# plaits_v50.net
KiCad netlist of a schematic drawn in EAGLE
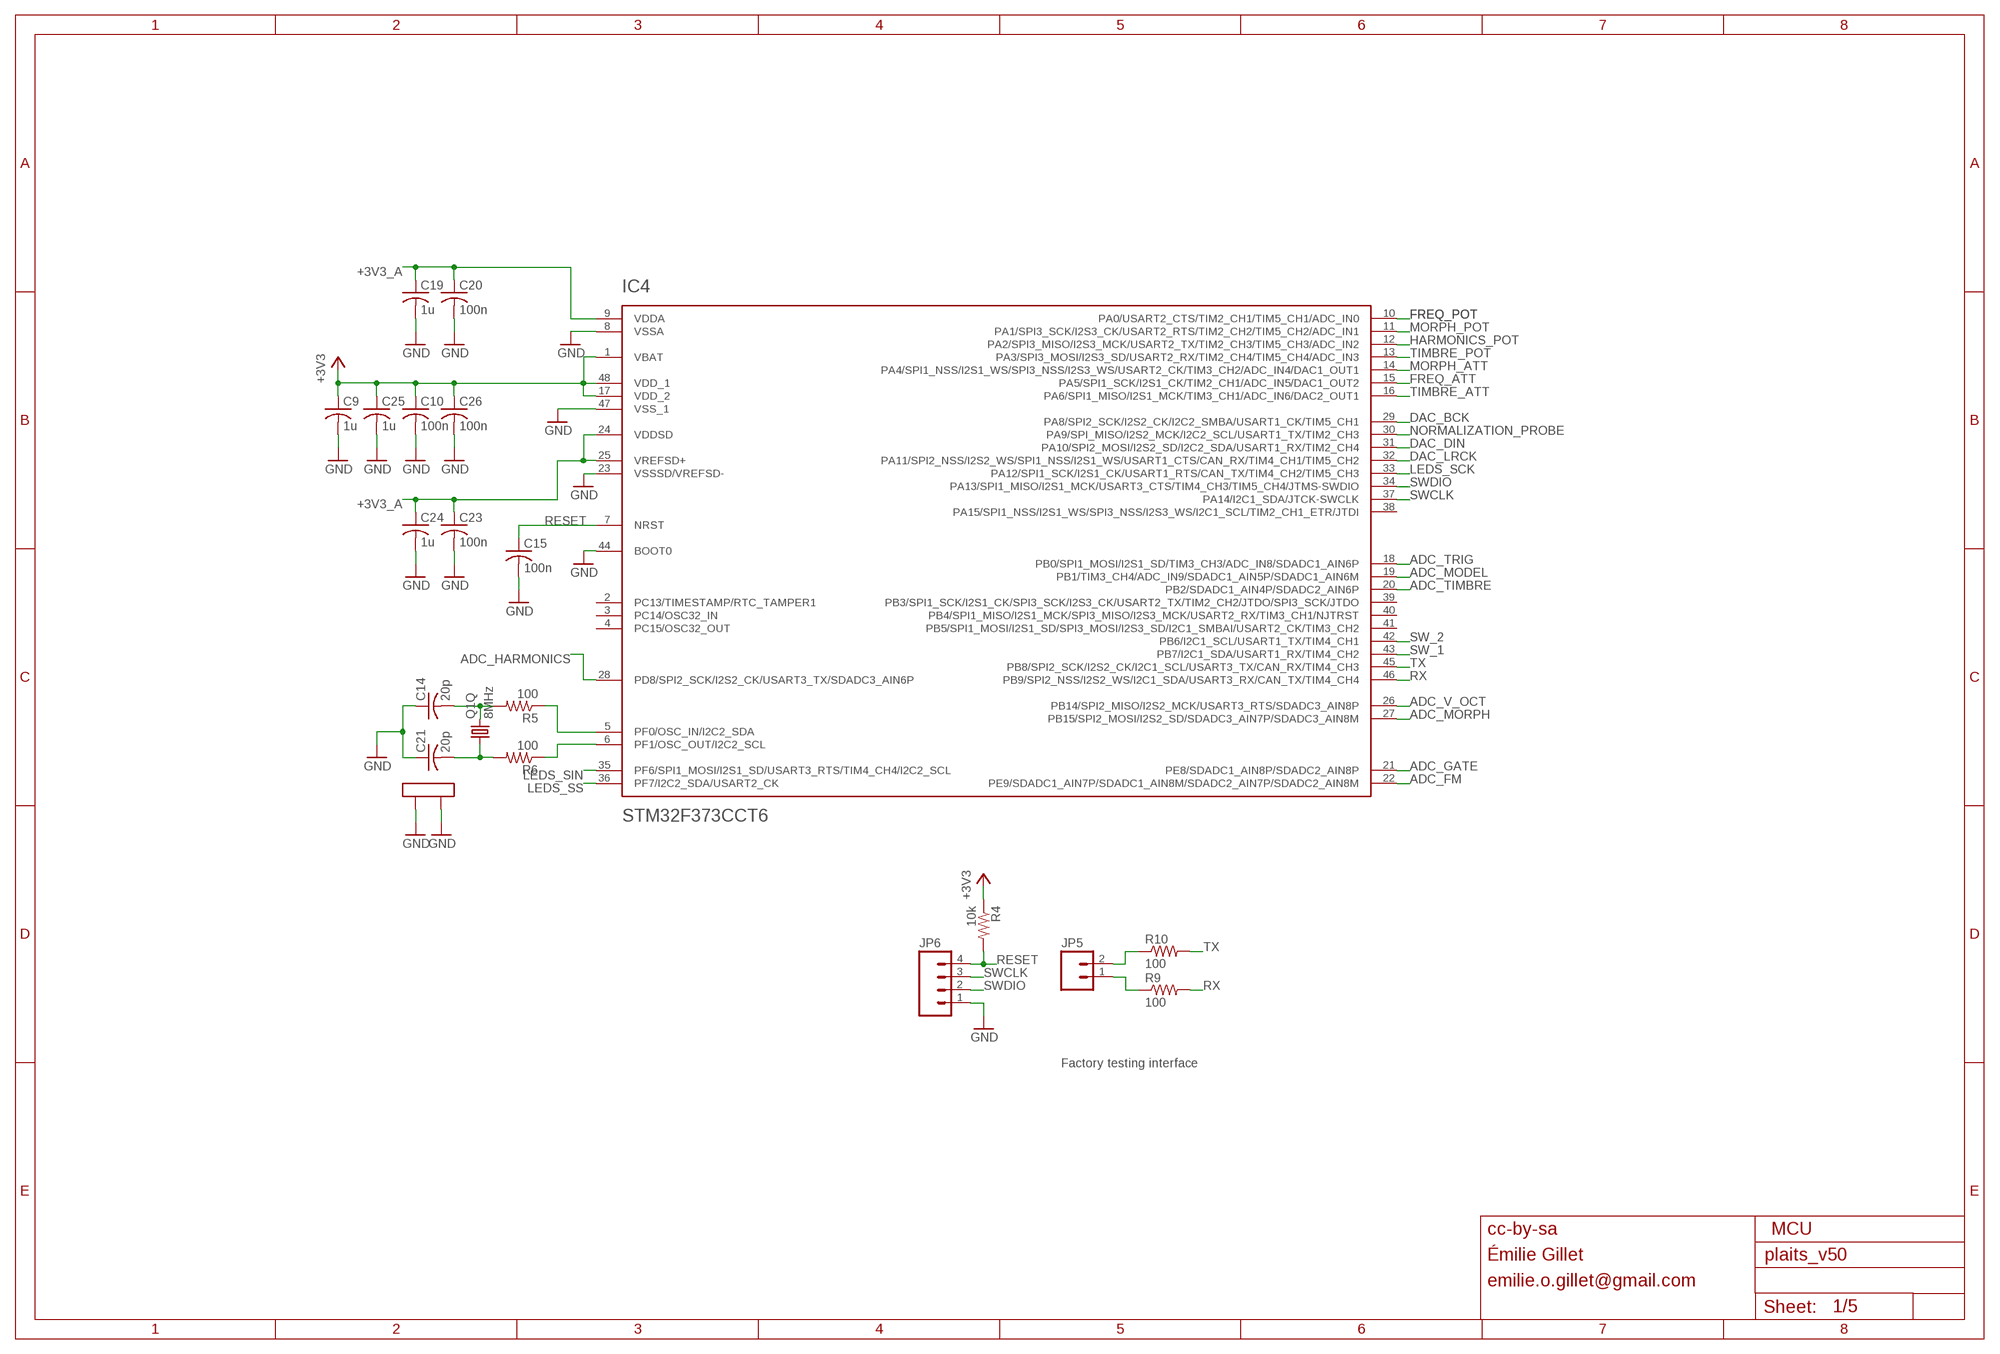
[diagram p0: schematic, sheet 1]
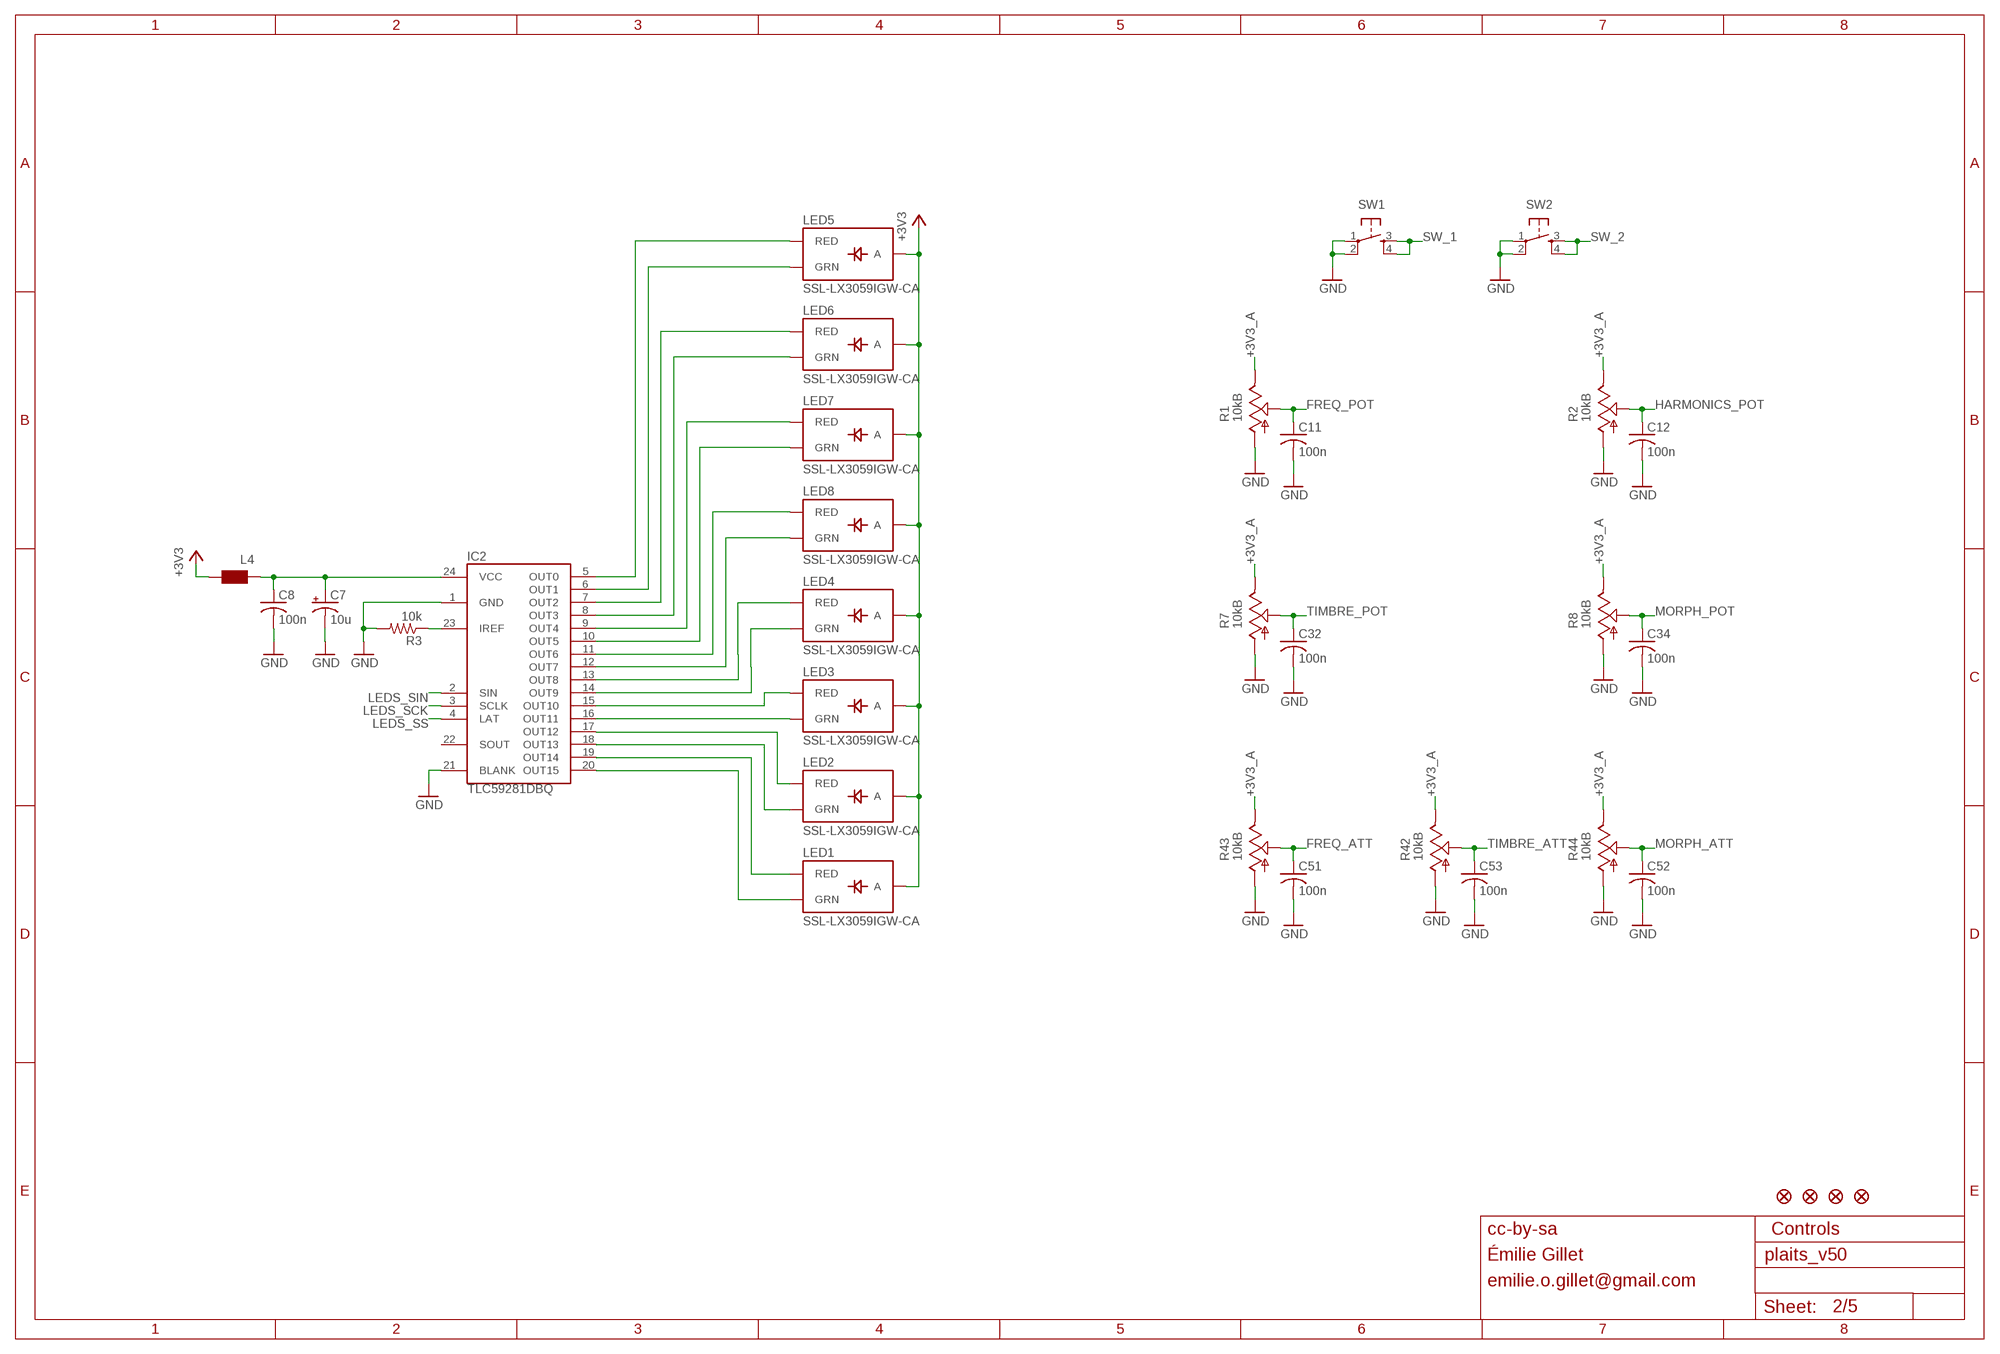
[diagram p1: schematic, sheet 2]
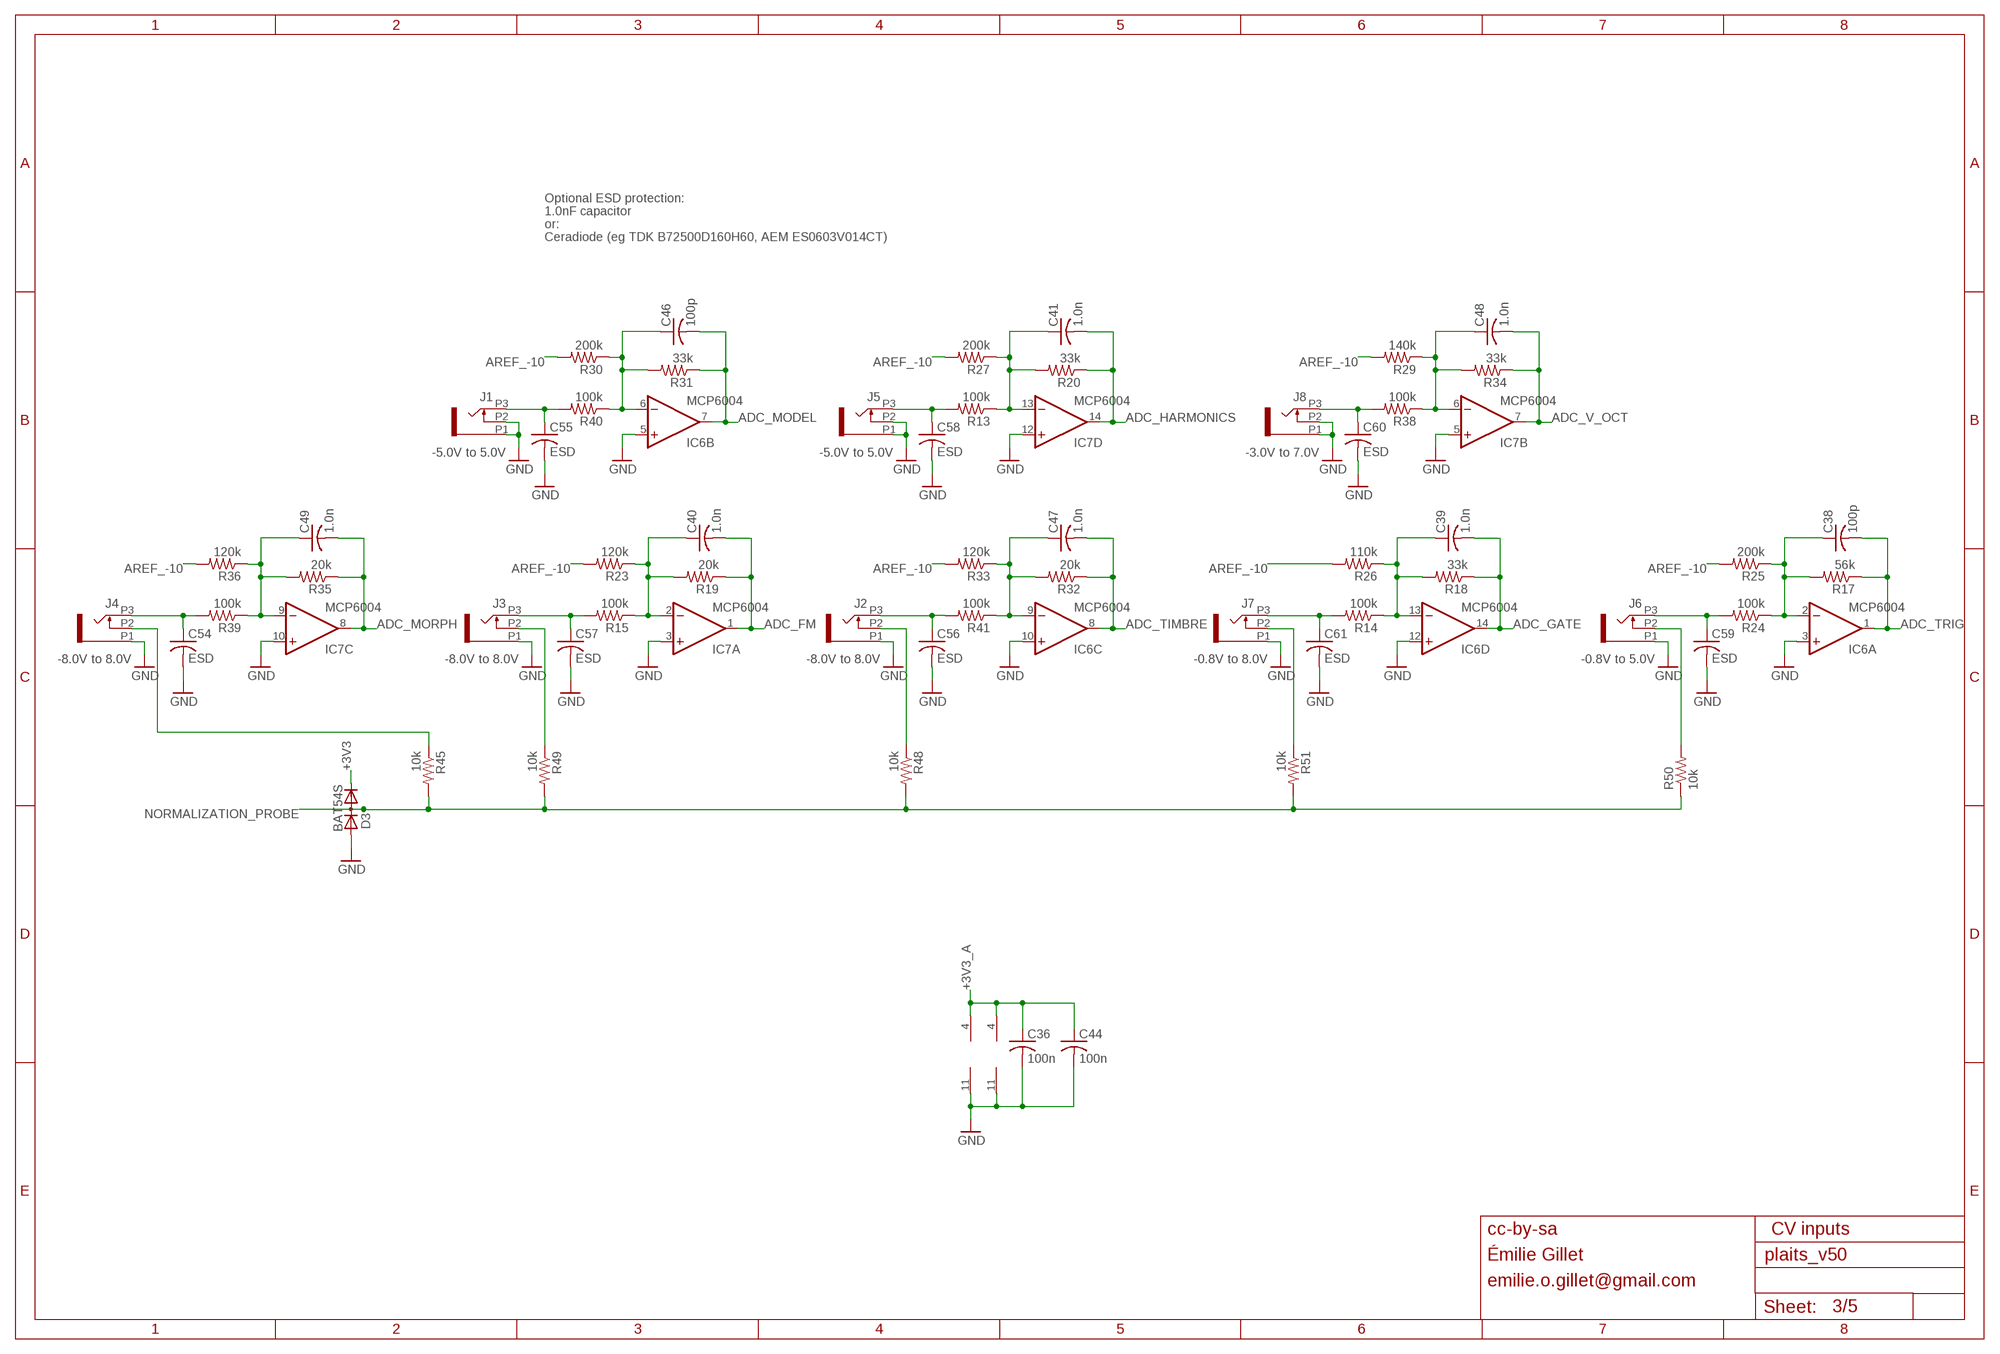
[diagram p2: schematic, sheet 3]
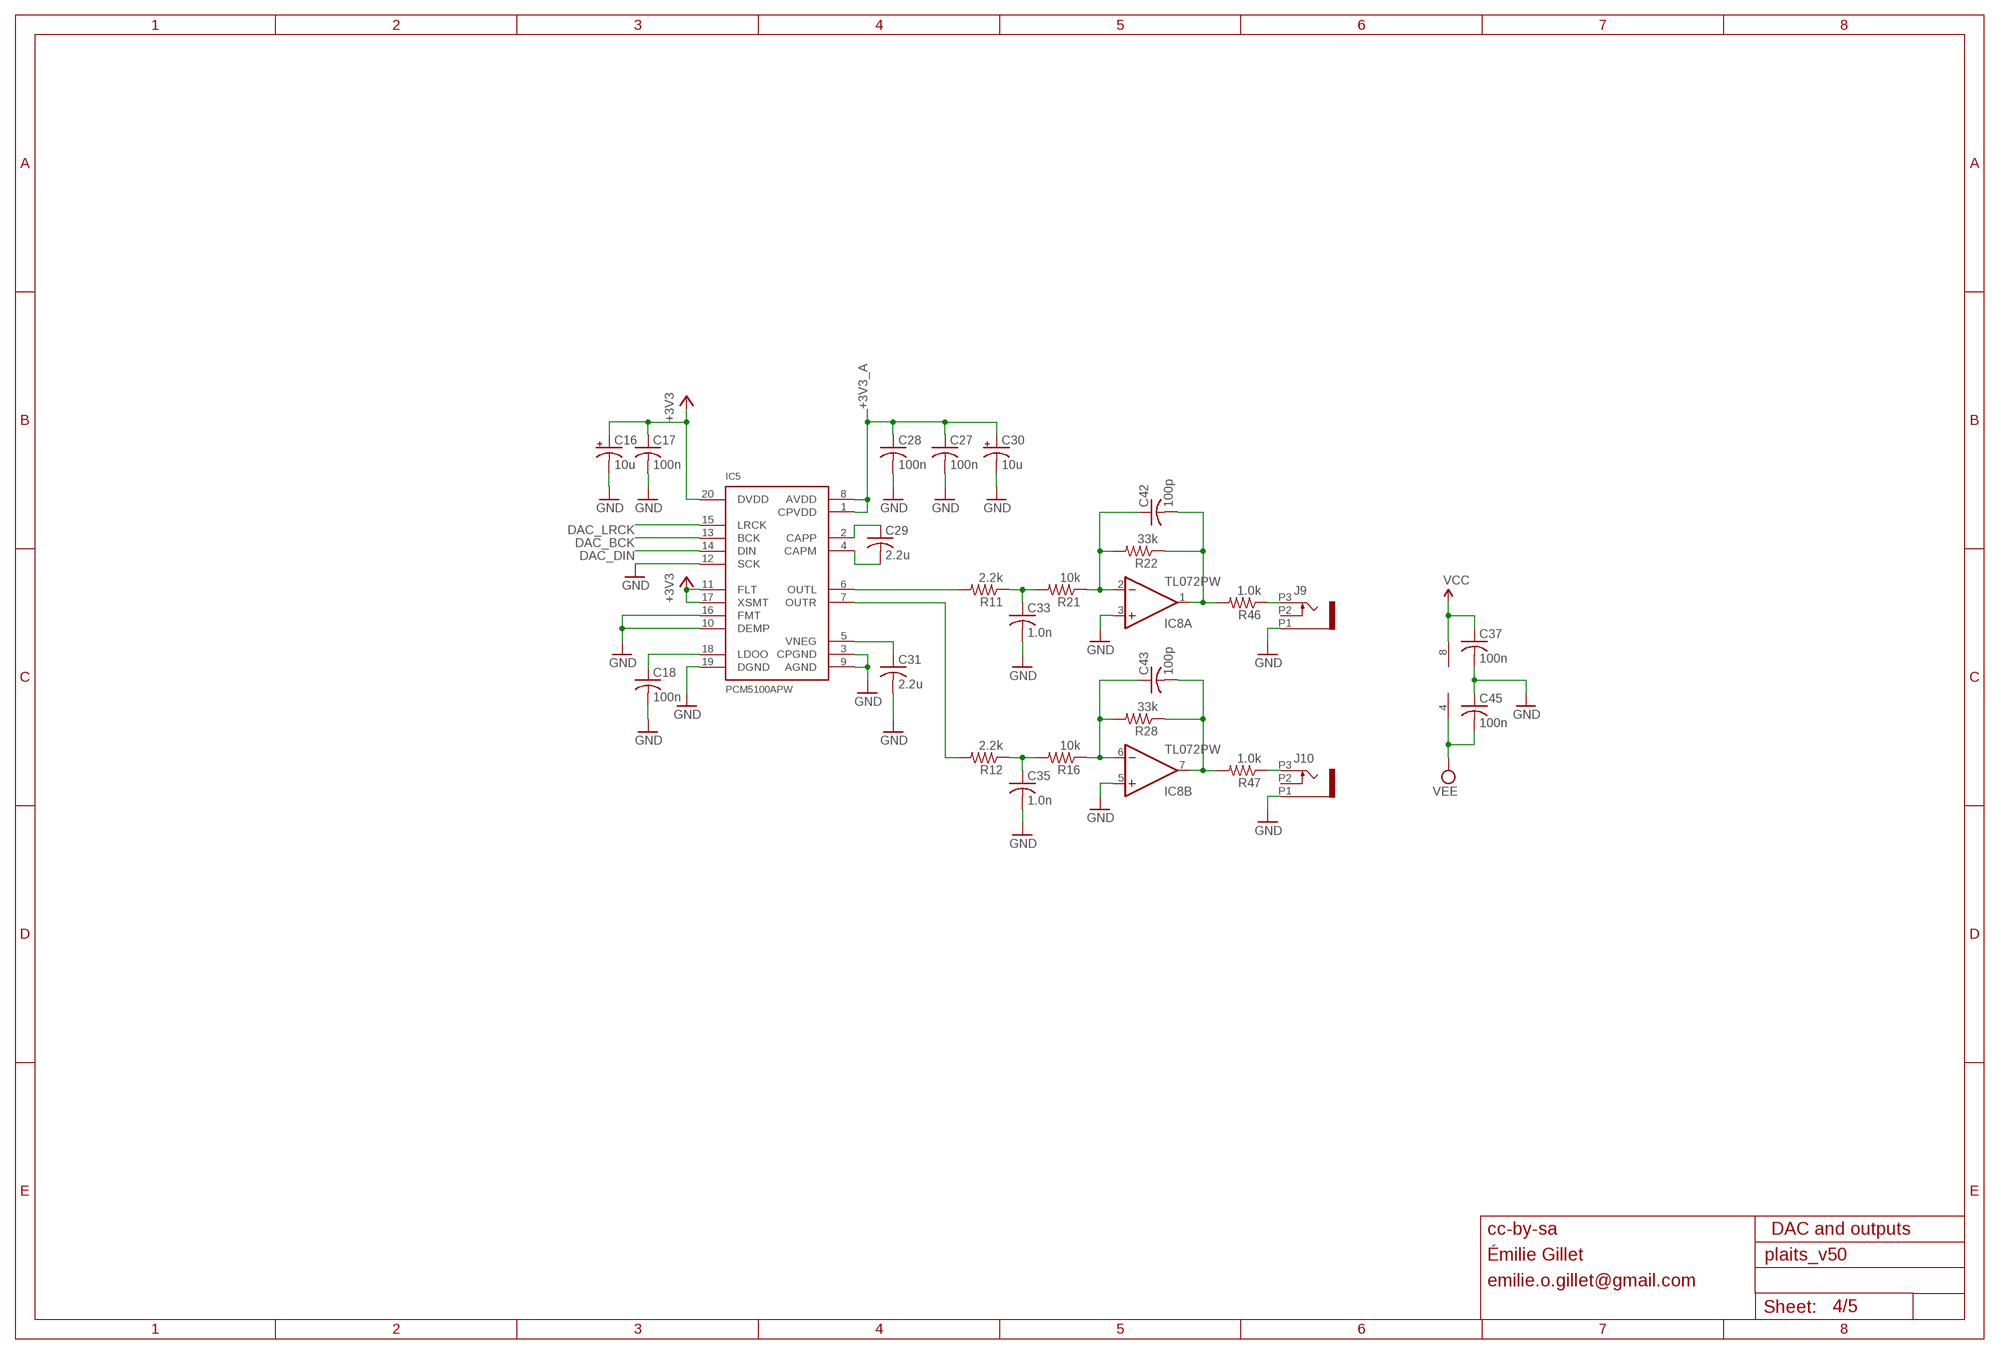
[diagram p3: schematic, sheet 4]
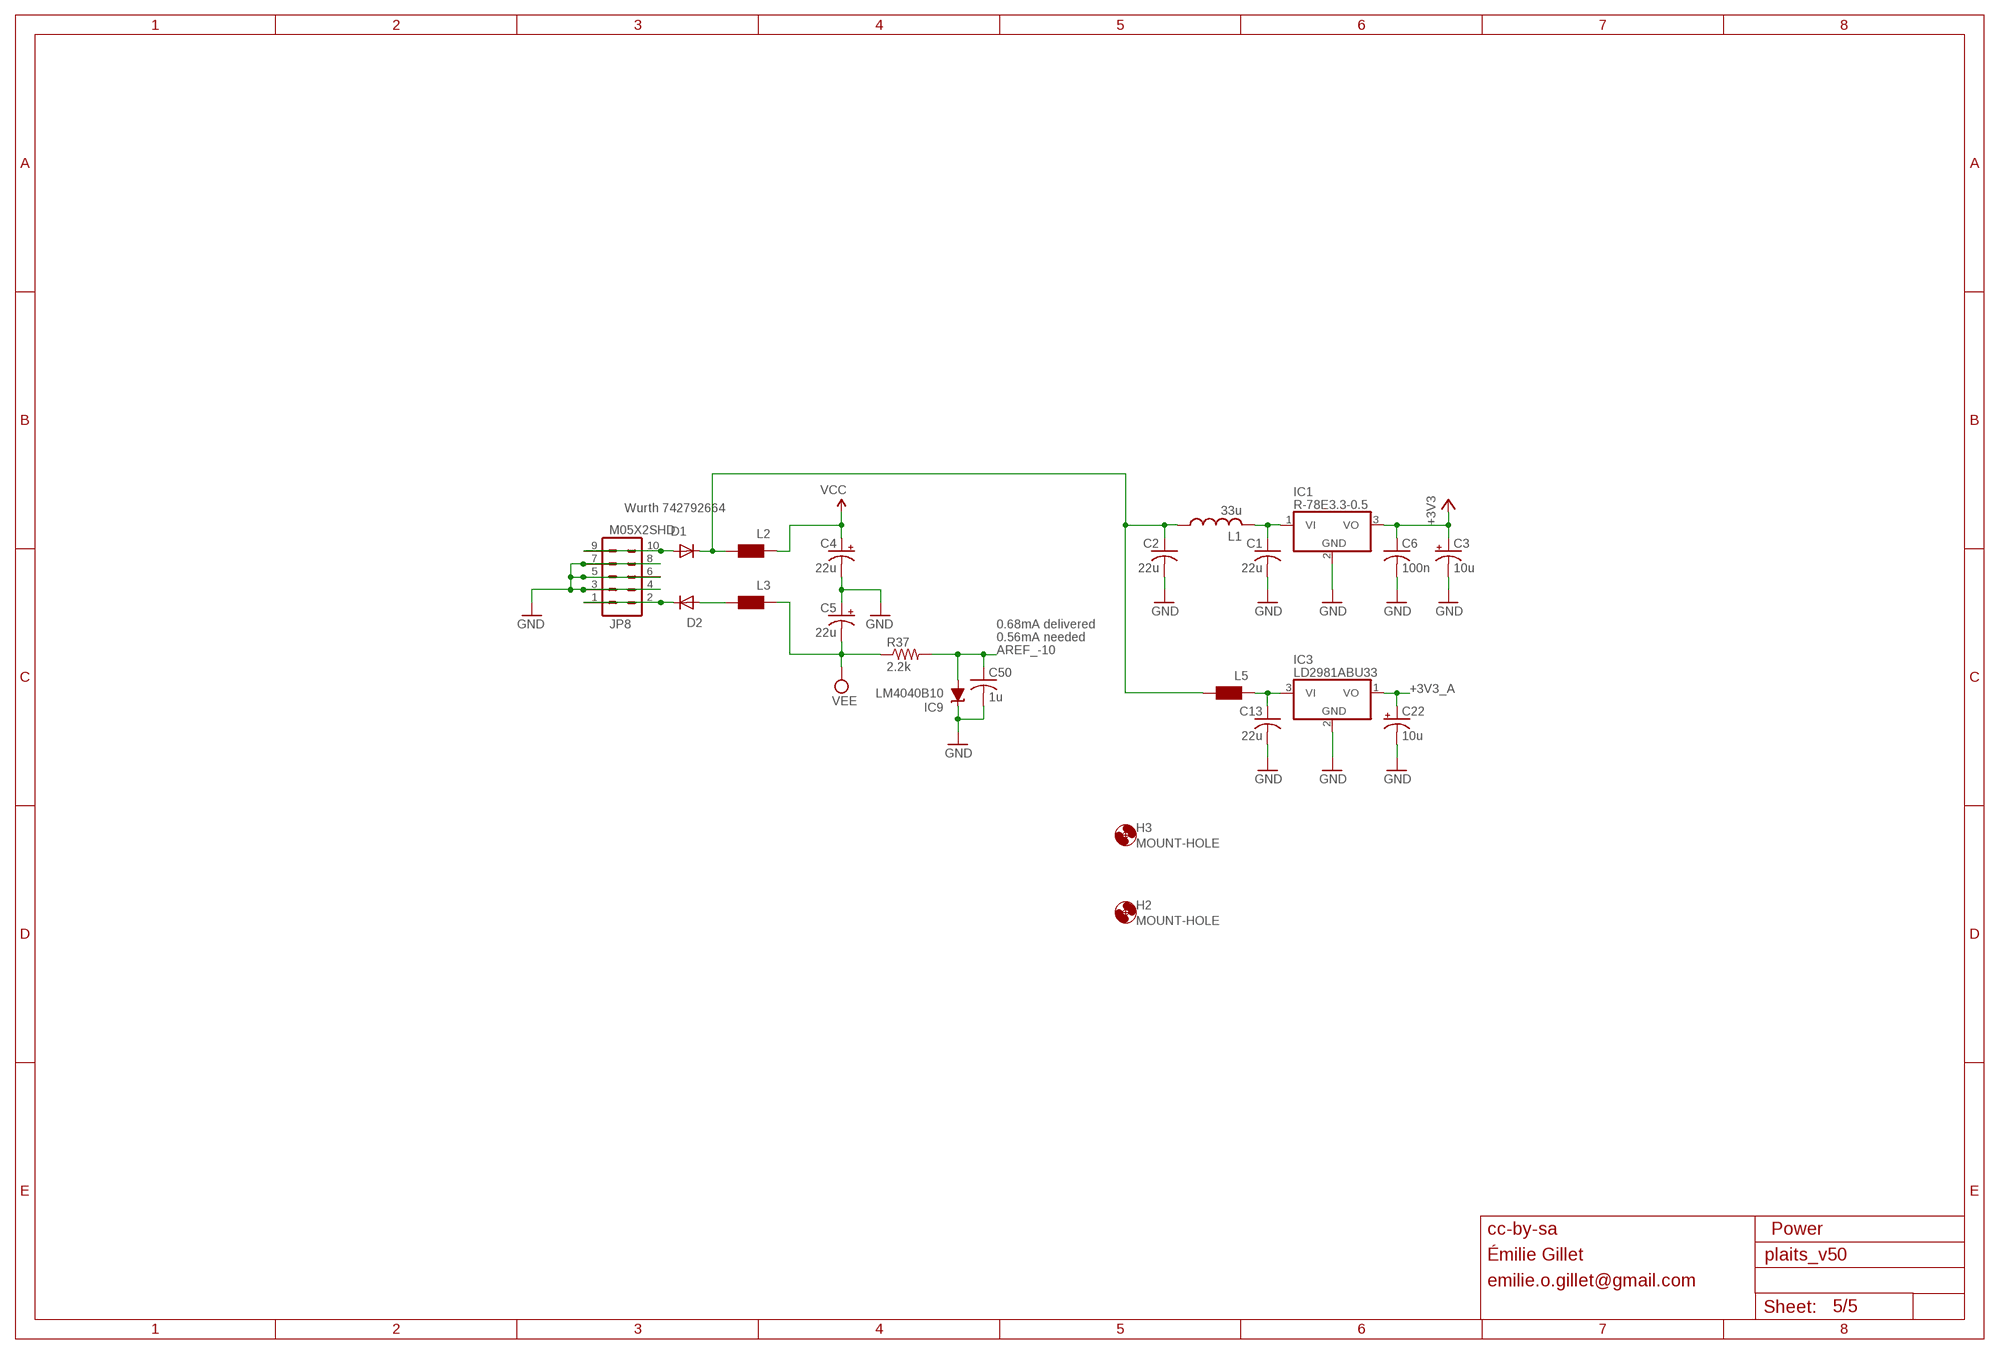
[diagram p4: schematic, sheet 5]

(export (version "E")
  (design (tool "Eeschema 10.0.6"))
  (components
    (comp (ref "C7")
      (value "10u")
      (footprint "eagle-import:PANASONIC_A")
      (libsource (lib "eagle-import") (part "CPOL-USA"))
    )
    (comp (ref "C8")
      (value "100n")
      (footprint "eagle-import:C0402")
      (libsource (lib "eagle-import") (part "C-USC0402"))
    )
    (comp (ref "C11")
      (value "100n")
      (footprint "eagle-import:C0402")
      (libsource (lib "eagle-import") (part "C-USC0402"))
    )
    (comp (ref "C12")
      (value "100n")
      (footprint "eagle-import:C0402")
      (libsource (lib "eagle-import") (part "C-USC0402"))
    )
    (comp (ref "C32")
      (value "100n")
      (footprint "eagle-import:C0402")
      (libsource (lib "eagle-import") (part "C-USC0402"))
    )
    (comp (ref "C34")
      (value "100n")
      (footprint "eagle-import:C0402")
      (libsource (lib "eagle-import") (part "C-USC0402"))
    )
    (comp (ref "C51")
      (value "100n")
      (footprint "eagle-import:C0402")
      (libsource (lib "eagle-import") (part "C-USC0402"))
    )
    (comp (ref "C52")
      (value "100n")
      (footprint "eagle-import:C0402")
      (libsource (lib "eagle-import") (part "C-USC0402"))
    )
    (comp (ref "C53")
      (value "100n")
      (footprint "eagle-import:C0402")
      (libsource (lib "eagle-import") (part "C-USC0402"))
    )
    (comp (ref "IC2")
      (value "TLC59281DBQ")
      (footprint "eagle-import:TSSOP24_0635")
      (libsource (lib "eagle-import") (part "TLC59281DBQ"))
    )
    (comp (ref "JP1")
      (value "FIDUCIAL1X2")
      (footprint "eagle-import:FIDUCIAL-1X2")
      (libsource (lib "eagle-import") (part "FIDUCIAL1X2"))
    )
    (comp (ref "JP2")
      (value "FIDUCIAL1X2")
      (footprint "eagle-import:FIDUCIAL-1X2")
      (libsource (lib "eagle-import") (part "FIDUCIAL1X2"))
    )
    (comp (ref "JP3")
      (value "FIDUCIAL1X2")
      (footprint "eagle-import:FIDUCIAL-1X2")
      (libsource (lib "eagle-import") (part "FIDUCIAL1X2"))
    )
    (comp (ref "JP4")
      (value "FIDUCIAL1X2")
      (footprint "eagle-import:FIDUCIAL-1X2")
      (libsource (lib "eagle-import") (part "FIDUCIAL1X2"))
    )
    (comp (ref "L4")
      (value "WE-CBF_0603")
      (footprint "eagle-import:0603")
      (libsource (lib "eagle-import") (part "WE-CBF_0603"))
    )
    (comp (ref "LED1")
      (value "SSL-LX3059IGW-CA")
      (footprint "eagle-import:LED-BICOLOR-THROUGHHOLE-LUMEX")
      (libsource (lib "eagle-import") (part "LED-BICOLOR-THROUGHHOLE-CA"))
    )
    (comp (ref "LED2")
      (value "SSL-LX3059IGW-CA")
      (footprint "eagle-import:LED-BICOLOR-THROUGHHOLE-LUMEX")
      (libsource (lib "eagle-import") (part "LED-BICOLOR-THROUGHHOLE-CA"))
    )
    (comp (ref "LED3")
      (value "SSL-LX3059IGW-CA")
      (footprint "eagle-import:LED-BICOLOR-THROUGHHOLE-LUMEX")
      (libsource (lib "eagle-import") (part "LED-BICOLOR-THROUGHHOLE-CA"))
    )
    (comp (ref "LED4")
      (value "SSL-LX3059IGW-CA")
      (footprint "eagle-import:LED-BICOLOR-THROUGHHOLE-LUMEX")
      (libsource (lib "eagle-import") (part "LED-BICOLOR-THROUGHHOLE-CA"))
    )
    (comp (ref "LED5")
      (value "SSL-LX3059IGW-CA")
      (footprint "eagle-import:LED-BICOLOR-THROUGHHOLE-LUMEX")
      (libsource (lib "eagle-import") (part "LED-BICOLOR-THROUGHHOLE-CA"))
    )
    (comp (ref "LED6")
      (value "SSL-LX3059IGW-CA")
      (footprint "eagle-import:LED-BICOLOR-THROUGHHOLE-LUMEX")
      (libsource (lib "eagle-import") (part "LED-BICOLOR-THROUGHHOLE-CA"))
    )
    (comp (ref "LED7")
      (value "SSL-LX3059IGW-CA")
      (footprint "eagle-import:LED-BICOLOR-THROUGHHOLE-LUMEX")
      (libsource (lib "eagle-import") (part "LED-BICOLOR-THROUGHHOLE-CA"))
    )
    (comp (ref "LED8")
      (value "SSL-LX3059IGW-CA")
      (footprint "eagle-import:LED-BICOLOR-THROUGHHOLE-LUMEX")
      (libsource (lib "eagle-import") (part "LED-BICOLOR-THROUGHHOLE-CA"))
    )
    (comp (ref "R1")
      (value "10kB")
      (footprint "eagle-import:ALPS_POT_VERTICAL_PS")
      (libsource (lib "eagle-import") (part "POT_USVERTICAL_PS"))
    )
    (comp (ref "R2")
      (value "10kB")
      (footprint "eagle-import:ALPS_POT_VERTICAL_PS")
      (libsource (lib "eagle-import") (part "POT_USVERTICAL_PS"))
    )
    (comp (ref "R3")
      (value "10k")
      (footprint "eagle-import:R0402")
      (libsource (lib "eagle-import") (part "R-US_R0402"))
    )
    (comp (ref "R7")
      (value "10kB")
      (footprint "eagle-import:ALPS_POT_VERTICAL_PS")
      (libsource (lib "eagle-import") (part "POT_USVERTICAL_PS"))
    )
    (comp (ref "R8")
      (value "10kB")
      (footprint "eagle-import:ALPS_POT_VERTICAL_PS")
      (libsource (lib "eagle-import") (part "POT_USVERTICAL_PS"))
    )
    (comp (ref "R42")
      (value "10kB")
      (footprint "eagle-import:ALPS_POT_VERTICAL")
      (libsource (lib "eagle-import") (part "POT_USVERTICAL"))
    )
    (comp (ref "R43")
      (value "10kB")
      (footprint "eagle-import:ALPS_POT_VERTICAL")
      (libsource (lib "eagle-import") (part "POT_USVERTICAL"))
    )
    (comp (ref "R44")
      (value "10kB")
      (footprint "eagle-import:ALPS_POT_VERTICAL")
      (libsource (lib "eagle-import") (part "POT_USVERTICAL"))
    )
    (comp (ref "SW1")
      (value "TAC_SWITCHPTH")
      (footprint "eagle-import:TACTILE-PTH")
      (libsource (lib "eagle-import") (part "TAC_SWITCHPTH"))
    )
    (comp (ref "SW2")
      (value "TAC_SWITCHPTH")
      (footprint "eagle-import:TACTILE-PTH")
      (libsource (lib "eagle-import") (part "TAC_SWITCHPTH"))
    )
    (comp (ref "C9")
      (value "1u")
      (footprint "eagle-import:C0402")
      (libsource (lib "eagle-import") (part "C-USC0402"))
    )
    (comp (ref "C10")
      (value "100n")
      (footprint "eagle-import:C0402")
      (libsource (lib "eagle-import") (part "C-USC0402"))
    )
    (comp (ref "C14")
      (value "20p")
      (footprint "eagle-import:C0402")
      (libsource (lib "eagle-import") (part "C-USC0402"))
    )
    (comp (ref "C15")
      (value "100n")
      (footprint "eagle-import:C0402")
      (libsource (lib "eagle-import") (part "C-USC0402"))
    )
    (comp (ref "C19")
      (value "1u")
      (footprint "eagle-import:C0402")
      (libsource (lib "eagle-import") (part "C-USC0402"))
    )
    (comp (ref "C20")
      (value "100n")
      (footprint "eagle-import:C0402")
      (libsource (lib "eagle-import") (part "C-USC0402"))
    )
    (comp (ref "C21")
      (value "20p")
      (footprint "eagle-import:C0402")
      (libsource (lib "eagle-import") (part "C-USC0402"))
    )
    (comp (ref "C23")
      (value "100n")
      (footprint "eagle-import:C0402")
      (libsource (lib "eagle-import") (part "C-USC0402"))
    )
    (comp (ref "C24")
      (value "1u")
      (footprint "eagle-import:C0402")
      (libsource (lib "eagle-import") (part "C-USC0402"))
    )
    (comp (ref "C25")
      (value "1u")
      (footprint "eagle-import:C0402")
      (libsource (lib "eagle-import") (part "C-USC0402"))
    )
    (comp (ref "C26")
      (value "100n")
      (footprint "eagle-import:C0402")
      (libsource (lib "eagle-import") (part "C-USC0402"))
    )
    (comp (ref "IC4")
      (value "STM32F373CCT6")
      (footprint "eagle-import:LQFP48")
      (libsource (lib "eagle-import") (part "STM32F373C"))
    )
    (comp (ref "JP5")
      (value "M02PTH")
      (footprint "eagle-import:1X02")
      (libsource (lib "eagle-import") (part "M02PTH"))
    )
    (comp (ref "JP6")
      (value "M04PTH")
      (footprint "eagle-import:1X04")
      (libsource (lib "eagle-import") (part "M04PTH"))
    )
    (comp (ref "Q1")
      (value "8MHz")
      (footprint "eagle-import:CTS406")
      (libsource (lib "eagle-import") (part "CRYSTAL"))
    )
    (comp (ref "R4")
      (value "10k")
      (footprint "eagle-import:R0402")
      (libsource (lib "eagle-import") (part "R-US_R0402"))
    )
    (comp (ref "R5")
      (value "100")
      (footprint "eagle-import:R0402")
      (libsource (lib "eagle-import") (part "R-US_R0402"))
    )
    (comp (ref "R6")
      (value "100")
      (footprint "eagle-import:R0402")
      (libsource (lib "eagle-import") (part "R-US_R0402"))
    )
    (comp (ref "R9")
      (value "100")
      (footprint "eagle-import:R0402")
      (libsource (lib "eagle-import") (part "R-US_R0402"))
    )
    (comp (ref "R10")
      (value "100")
      (footprint "eagle-import:R0402")
      (libsource (lib "eagle-import") (part "R-US_R0402"))
    )
    (comp (ref "C16")
      (value "10u")
      (footprint "eagle-import:PANASONIC_A")
      (libsource (lib "eagle-import") (part "CPOL-USA"))
    )
    (comp (ref "C17")
      (value "100n")
      (footprint "eagle-import:C0402")
      (libsource (lib "eagle-import") (part "C-USC0402"))
    )
    (comp (ref "C18")
      (value "100n")
      (footprint "eagle-import:C0402")
      (libsource (lib "eagle-import") (part "C-USC0402"))
    )
    (comp (ref "C27")
      (value "100n")
      (footprint "eagle-import:C0402")
      (libsource (lib "eagle-import") (part "C-USC0402"))
    )
    (comp (ref "C28")
      (value "100n")
      (footprint "eagle-import:C0402")
      (libsource (lib "eagle-import") (part "C-USC0402"))
    )
    (comp (ref "C29")
      (value "2.2u")
      (footprint "eagle-import:C0805")
      (libsource (lib "eagle-import") (part "C-USC0805"))
    )
    (comp (ref "C30")
      (value "10u")
      (footprint "eagle-import:PANASONIC_A")
      (libsource (lib "eagle-import") (part "CPOL-USA"))
    )
    (comp (ref "C31")
      (value "2.2u")
      (footprint "eagle-import:C0805")
      (libsource (lib "eagle-import") (part "C-USC0805"))
    )
    (comp (ref "C33")
      (value "1.0n")
      (footprint "eagle-import:C0402")
      (libsource (lib "eagle-import") (part "C-USC0402"))
    )
    (comp (ref "C35")
      (value "1.0n")
      (footprint "eagle-import:C0402")
      (libsource (lib "eagle-import") (part "C-USC0402"))
    )
    (comp (ref "C37")
      (value "100n")
      (footprint "eagle-import:C0402")
      (libsource (lib "eagle-import") (part "C-USC0402"))
    )
    (comp (ref "C42")
      (value "100p")
      (footprint "eagle-import:C0402")
      (libsource (lib "eagle-import") (part "C-USC0402"))
    )
    (comp (ref "C43")
      (value "100p")
      (footprint "eagle-import:C0402")
      (libsource (lib "eagle-import") (part "C-USC0402"))
    )
    (comp (ref "C45")
      (value "100n")
      (footprint "eagle-import:C0402")
      (libsource (lib "eagle-import") (part "C-USC0402"))
    )
    (comp (ref "IC5")
      (value "PCM5100APW")
      (footprint "eagle-import:SSOP20")
      (libsource (lib "eagle-import") (part "PCM5100PW"))
    )
    (comp (ref "IC8")
      (value "TL072PW")
      (footprint "eagle-import:TSSOP08")
      (libsource (lib "eagle-import") (part "TL072PW"))
    )
    (comp (ref "J9")
      (value "PJ301_THONKICONN6")
      (footprint "eagle-import:WQP_PJ_301M6")
      (libsource (lib "eagle-import") (part "PJ301_THONKICONN6"))
    )
    (comp (ref "J10")
      (value "PJ301_THONKICONN6")
      (footprint "eagle-import:WQP_PJ_301M6")
      (libsource (lib "eagle-import") (part "PJ301_THONKICONN6"))
    )
    (comp (ref "R11")
      (value "2.2k")
      (footprint "eagle-import:R0402")
      (libsource (lib "eagle-import") (part "R-US_R0402"))
    )
    (comp (ref "R12")
      (value "2.2k")
      (footprint "eagle-import:R0402")
      (libsource (lib "eagle-import") (part "R-US_R0402"))
    )
    (comp (ref "R16")
      (value "10k")
      (footprint "eagle-import:R0402")
      (libsource (lib "eagle-import") (part "R-US_R0402"))
    )
    (comp (ref "R21")
      (value "10k")
      (footprint "eagle-import:R0402")
      (libsource (lib "eagle-import") (part "R-US_R0402"))
    )
    (comp (ref "R22")
      (value "33k")
      (footprint "eagle-import:R0402")
      (libsource (lib "eagle-import") (part "R-US_R0402"))
    )
    (comp (ref "R28")
      (value "33k")
      (footprint "eagle-import:R0402")
      (libsource (lib "eagle-import") (part "R-US_R0402"))
    )
    (comp (ref "R46")
      (value "1.0k")
      (footprint "eagle-import:R0603")
      (libsource (lib "eagle-import") (part "R-US_R0603"))
    )
    (comp (ref "R47")
      (value "1.0k")
      (footprint "eagle-import:R0603")
      (libsource (lib "eagle-import") (part "R-US_R0603"))
    )
    (comp (ref "C36")
      (value "100n")
      (footprint "eagle-import:C0402")
      (libsource (lib "eagle-import") (part "C-USC0402"))
    )
    (comp (ref "C38")
      (value "100p")
      (footprint "eagle-import:C0402")
      (libsource (lib "eagle-import") (part "C-USC0402"))
    )
    (comp (ref "C39")
      (value "1.0n")
      (footprint "eagle-import:C0402")
      (libsource (lib "eagle-import") (part "C-USC0402"))
    )
    (comp (ref "C40")
      (value "1.0n")
      (footprint "eagle-import:C0402")
      (libsource (lib "eagle-import") (part "C-USC0402"))
    )
    (comp (ref "C41")
      (value "1.0n")
      (footprint "eagle-import:C0402")
      (libsource (lib "eagle-import") (part "C-USC0402"))
    )
    (comp (ref "C44")
      (value "100n")
      (footprint "eagle-import:C0402")
      (libsource (lib "eagle-import") (part "C-USC0402"))
    )
    (comp (ref "C46")
      (value "100p")
      (footprint "eagle-import:C0402")
      (libsource (lib "eagle-import") (part "C-USC0402"))
    )
    (comp (ref "C47")
      (value "1.0n")
      (footprint "eagle-import:C0402")
      (libsource (lib "eagle-import") (part "C-USC0402"))
    )
    (comp (ref "C48")
      (value "1.0n")
      (footprint "eagle-import:C0402")
      (libsource (lib "eagle-import") (part "C-USC0402"))
    )
    (comp (ref "C49")
      (value "1.0n")
      (footprint "eagle-import:C0402")
      (libsource (lib "eagle-import") (part "C-USC0402"))
    )
    (comp (ref "C54")
      (value "ESD")
      (footprint "eagle-import:C0603")
      (libsource (lib "eagle-import") (part "C-USC0603"))
    )
    (comp (ref "C55")
      (value "ESD")
      (footprint "eagle-import:C0603")
      (libsource (lib "eagle-import") (part "C-USC0603"))
    )
    (comp (ref "C56")
      (value "ESD")
      (footprint "eagle-import:C0603")
      (libsource (lib "eagle-import") (part "C-USC0603"))
    )
    (comp (ref "C57")
      (value "ESD")
      (footprint "eagle-import:C0603")
      (libsource (lib "eagle-import") (part "C-USC0603"))
    )
    (comp (ref "C58")
      (value "ESD")
      (footprint "eagle-import:C0603")
      (libsource (lib "eagle-import") (part "C-USC0603"))
    )
    (comp (ref "C59")
      (value "ESD")
      (footprint "eagle-import:C0603")
      (libsource (lib "eagle-import") (part "C-USC0603"))
    )
    (comp (ref "C60")
      (value "ESD")
      (footprint "eagle-import:C0603")
      (libsource (lib "eagle-import") (part "C-USC0603"))
    )
    (comp (ref "C61")
      (value "ESD")
      (footprint "eagle-import:C0603")
      (libsource (lib "eagle-import") (part "C-USC0603"))
    )
    (comp (ref "D3")
      (value "BAT54S")
      (footprint "eagle-import:SOT23")
      (libsource (lib "eagle-import") (part "DIODE_2CACA-SOT23"))
    )
    (comp (ref "IC6")
      (value "MCP6004")
      (footprint "eagle-import:TSSOP14_065")
      (libsource (lib "eagle-import") (part "TL074PW"))
    )
    (comp (ref "IC7")
      (value "MCP6004")
      (footprint "eagle-import:TSSOP14_065")
      (libsource (lib "eagle-import") (part "TL074PW"))
    )
    (comp (ref "J1")
      (value "PJ301_THONKICONN6")
      (footprint "eagle-import:WQP_PJ_301M6")
      (libsource (lib "eagle-import") (part "PJ301_THONKICONN6"))
    )
    (comp (ref "J2")
      (value "PJ301_THONKICONN6")
      (footprint "eagle-import:WQP_PJ_301M6")
      (libsource (lib "eagle-import") (part "PJ301_THONKICONN6"))
    )
    (comp (ref "J3")
      (value "PJ301_THONKICONN6")
      (footprint "eagle-import:WQP_PJ_301M6")
      (libsource (lib "eagle-import") (part "PJ301_THONKICONN6"))
    )
    (comp (ref "J4")
      (value "PJ301_THONKICONN6")
      (footprint "eagle-import:WQP_PJ_301M6")
      (libsource (lib "eagle-import") (part "PJ301_THONKICONN6"))
    )
    (comp (ref "J5")
      (value "PJ301_THONKICONN6")
      (footprint "eagle-import:WQP_PJ_301M6")
      (libsource (lib "eagle-import") (part "PJ301_THONKICONN6"))
    )
    (comp (ref "J6")
      (value "PJ301_THONKICONN6")
      (footprint "eagle-import:WQP_PJ_301M6")
      (libsource (lib "eagle-import") (part "PJ301_THONKICONN6"))
    )
    (comp (ref "J7")
      (value "PJ301_THONKICONN6")
      (footprint "eagle-import:WQP_PJ_301M6")
      (libsource (lib "eagle-import") (part "PJ301_THONKICONN6"))
    )
    (comp (ref "J8")
      (value "PJ301_THONKICONN6")
      (footprint "eagle-import:WQP_PJ_301M6")
      (libsource (lib "eagle-import") (part "PJ301_THONKICONN6"))
    )
    (comp (ref "R13")
      (value "100k")
      (footprint "eagle-import:R0402")
      (libsource (lib "eagle-import") (part "R-US_R0402"))
    )
    (comp (ref "R14")
      (value "100k")
      (footprint "eagle-import:R0402")
      (libsource (lib "eagle-import") (part "R-US_R0402"))
    )
    (comp (ref "R15")
      (value "100k")
      (footprint "eagle-import:R0402")
      (libsource (lib "eagle-import") (part "R-US_R0402"))
    )
    (comp (ref "R17")
      (value "56k")
      (footprint "eagle-import:R0402")
      (libsource (lib "eagle-import") (part "R-US_R0402"))
    )
    (comp (ref "R18")
      (value "33k")
      (footprint "eagle-import:R0402")
      (libsource (lib "eagle-import") (part "R-US_R0402"))
    )
    (comp (ref "R19")
      (value "20k")
      (footprint "eagle-import:R0402")
      (libsource (lib "eagle-import") (part "R-US_R0402"))
    )
    (comp (ref "R20")
      (value "33k")
      (footprint "eagle-import:R0402")
      (libsource (lib "eagle-import") (part "R-US_R0402"))
    )
    (comp (ref "R23")
      (value "120k")
      (footprint "eagle-import:R0402")
      (libsource (lib "eagle-import") (part "R-US_R0402"))
    )
    (comp (ref "R24")
      (value "100k")
      (footprint "eagle-import:R0402")
      (libsource (lib "eagle-import") (part "R-US_R0402"))
    )
    (comp (ref "R25")
      (value "200k")
      (footprint "eagle-import:R0402")
      (libsource (lib "eagle-import") (part "R-US_R0402"))
    )
    (comp (ref "R26")
      (value "110k")
      (footprint "eagle-import:R0402")
      (libsource (lib "eagle-import") (part "R-US_R0402"))
    )
    (comp (ref "R27")
      (value "200k")
      (footprint "eagle-import:R0402")
      (libsource (lib "eagle-import") (part "R-US_R0402"))
    )
    (comp (ref "R29")
      (value "140k")
      (footprint "eagle-import:R0402")
      (libsource (lib "eagle-import") (part "R-US_R0402"))
    )
    (comp (ref "R30")
      (value "200k")
      (footprint "eagle-import:R0402")
      (libsource (lib "eagle-import") (part "R-US_R0402"))
    )
    (comp (ref "R31")
      (value "33k")
      (footprint "eagle-import:R0402")
      (libsource (lib "eagle-import") (part "R-US_R0402"))
    )
    (comp (ref "R32")
      (value "20k")
      (footprint "eagle-import:R0402")
      (libsource (lib "eagle-import") (part "R-US_R0402"))
    )
    (comp (ref "R33")
      (value "120k")
      (footprint "eagle-import:R0402")
      (libsource (lib "eagle-import") (part "R-US_R0402"))
    )
    (comp (ref "R34")
      (value "33k")
      (footprint "eagle-import:R0402")
      (libsource (lib "eagle-import") (part "R-US_R0402"))
    )
    (comp (ref "R35")
      (value "20k")
      (footprint "eagle-import:R0402")
      (libsource (lib "eagle-import") (part "R-US_R0402"))
    )
    (comp (ref "R36")
      (value "120k")
      (footprint "eagle-import:R0402")
      (libsource (lib "eagle-import") (part "R-US_R0402"))
    )
    (comp (ref "R38")
      (value "100k")
      (footprint "eagle-import:R0402")
      (libsource (lib "eagle-import") (part "R-US_R0402"))
    )
    (comp (ref "R39")
      (value "100k")
      (footprint "eagle-import:R0402")
      (libsource (lib "eagle-import") (part "R-US_R0402"))
    )
    (comp (ref "R40")
      (value "100k")
      (footprint "eagle-import:R0402")
      (libsource (lib "eagle-import") (part "R-US_R0402"))
    )
    (comp (ref "R41")
      (value "100k")
      (footprint "eagle-import:R0402")
      (libsource (lib "eagle-import") (part "R-US_R0402"))
    )
    (comp (ref "R45")
      (value "10k")
      (footprint "eagle-import:R0402")
      (libsource (lib "eagle-import") (part "R-US_R0402"))
    )
    (comp (ref "R48")
      (value "10k")
      (footprint "eagle-import:R0402")
      (libsource (lib "eagle-import") (part "R-US_R0402"))
    )
    (comp (ref "R49")
      (value "10k")
      (footprint "eagle-import:R0402")
      (libsource (lib "eagle-import") (part "R-US_R0402"))
    )
    (comp (ref "R50")
      (value "10k")
      (footprint "eagle-import:R0402")
      (libsource (lib "eagle-import") (part "R-US_R0402"))
    )
    (comp (ref "R51")
      (value "10k")
      (footprint "eagle-import:R0402")
      (libsource (lib "eagle-import") (part "R-US_R0402"))
    )
    (comp (ref "C1")
      (value "22u")
      (footprint "eagle-import:C1206")
      (libsource (lib "eagle-import") (part "C-USC1206"))
    )
    (comp (ref "C2")
      (value "22u")
      (footprint "eagle-import:C1206")
      (libsource (lib "eagle-import") (part "C-USC1206"))
    )
    (comp (ref "C3")
      (value "10u")
      (footprint "eagle-import:PANASONIC_A")
      (libsource (lib "eagle-import") (part "CPOL-USA"))
    )
    (comp (ref "C4")
      (value "22u")
      (footprint "eagle-import:PANASONIC_B")
      (libsource (lib "eagle-import") (part "CPOL-USB"))
    )
    (comp (ref "C5")
      (value "22u")
      (footprint "eagle-import:PANASONIC_B")
      (libsource (lib "eagle-import") (part "CPOL-USB"))
    )
    (comp (ref "C6")
      (value "100n")
      (footprint "eagle-import:C0402")
      (libsource (lib "eagle-import") (part "C-USC0402"))
    )
    (comp (ref "C13")
      (value "22u")
      (footprint "eagle-import:C1206")
      (libsource (lib "eagle-import") (part "C-USC1206"))
    )
    (comp (ref "C22")
      (value "10u")
      (footprint "eagle-import:PANASONIC_A")
      (libsource (lib "eagle-import") (part "CPOL-USA"))
    )
    (comp (ref "C50")
      (value "1u")
      (footprint "eagle-import:C0402")
      (libsource (lib "eagle-import") (part "C-USC0402"))
    )
    (comp (ref "D1")
      (value "1N5819HW")
      (footprint "eagle-import:SOD123")
      (libsource (lib "eagle-import") (part "DIODE-SOD123"))
    )
    (comp (ref "D2")
      (value "1N5819HW")
      (footprint "eagle-import:SOD123")
      (libsource (lib "eagle-import") (part "DIODE-SOD123"))
    )
    (comp (ref "H2")
      (value "MOUNT-HOLE")
      (footprint "eagle-import:3,0TINY")
      (libsource (lib "eagle-import") (part "MOUNT-HOLE3.0TINY"))
    )
    (comp (ref "H3")
      (value "MOUNT-HOLE")
      (footprint "eagle-import:3,0TINY")
      (libsource (lib "eagle-import") (part "MOUNT-HOLE3.0TINY"))
    )
    (comp (ref "IC1")
      (value "R-78E3.3-0.5")
      (footprint "eagle-import:WE78")
      (libsource (lib "eagle-import") (part "WE173950378"))
    )
    (comp (ref "IC3")
      (value "LD2981ABU33")
      (footprint "eagle-import:SOT89")
      (libsource (lib "eagle-import") (part "LD2981ABU"))
    )
    (comp (ref "IC9")
      (value "LM4040B10")
      (footprint "eagle-import:DBZ_R-PDSO-G3")
      (libsource (lib "eagle-import") (part "LM4041DBZB12"))
    )
    (comp (ref "JP8")
      (value "M05X2SHD")
      (footprint "eagle-import:2X5-SHROUDED")
      (libsource (lib "eagle-import") (part "M05X2SHD"))
    )
    (comp (ref "L1")
      (value "33u")
      (footprint "eagle-import:L2012C")
      (libsource (lib "eagle-import") (part "L-USL2012C"))
    )
    (comp (ref "L2")
      (value "WE-CBF_0603")
      (footprint "eagle-import:0603")
      (libsource (lib "eagle-import") (part "WE-CBF_0603"))
    )
    (comp (ref "L3")
      (value "WE-CBF_0603")
      (footprint "eagle-import:0603")
      (libsource (lib "eagle-import") (part "WE-CBF_0603"))
    )
    (comp (ref "L5")
      (value "WE-CBF_0603")
      (footprint "eagle-import:0603")
      (libsource (lib "eagle-import") (part "WE-CBF_0603"))
    )
    (comp (ref "R37")
      (value "2.2k")
      (footprint "eagle-import:R0402")
      (libsource (lib "eagle-import") (part "R-US_R0402"))
    )
  )
  (nets
    (net (code "1") (name "+3V3") (class "Default")
      (node (ref "C10") (pin "1") (pinfunction "1_1") (pintype "passive"))
      (node (ref "C16") (pin "+") (pinfunction "+_+") (pintype "passive"))
      (node (ref "C17") (pin "1") (pinfunction "1_1") (pintype "passive"))
      (node (ref "C25") (pin "1") (pinfunction "1_1") (pintype "passive"))
      (node (ref "C26") (pin "1") (pinfunction "1_1") (pintype "passive"))
      (node (ref "C3") (pin "+") (pinfunction "+_+") (pintype "passive"))
      (node (ref "C6") (pin "1") (pinfunction "1_1") (pintype "passive"))
      (node (ref "C9") (pin "1") (pinfunction "1_1") (pintype "passive"))
      (node (ref "D3") (pin "2") (pinfunction "C_2") (pintype "passive"))
      (node (ref "IC1") (pin "3") (pinfunction "VO_3") (pintype "passive"))
      (node (ref "IC4") (pin "1") (pinfunction "VBAT_1") (pintype "power_in"))
      (node (ref "IC4") (pin "17") (pinfunction "VDD_2_17") (pintype "power_in"))
      (node (ref "IC4") (pin "48") (pinfunction "VDD_1_48") (pintype "power_in"))
      (node (ref "IC5") (pin "11") (pinfunction "FLT_11") (pintype "input"))
      (node (ref "IC5") (pin "17") (pinfunction "XSMT_17") (pintype "input"))
      (node (ref "IC5") (pin "20") (pinfunction "DVDD_20") (pintype "power_in"))
      (node (ref "L4") (pin "2") (pinfunction "2_2") (pintype "passive"))
      (node (ref "LED1") (pin "A") (pinfunction "A_A") (pintype "bidirectional"))
      (node (ref "LED2") (pin "A") (pinfunction "A_A") (pintype "bidirectional"))
      (node (ref "LED3") (pin "A") (pinfunction "A_A") (pintype "bidirectional"))
      (node (ref "LED4") (pin "A") (pinfunction "A_A") (pintype "bidirectional"))
      (node (ref "LED5") (pin "A") (pinfunction "A_A") (pintype "bidirectional"))
      (node (ref "LED6") (pin "A") (pinfunction "A_A") (pintype "bidirectional"))
      (node (ref "LED7") (pin "A") (pinfunction "A_A") (pintype "bidirectional"))
      (node (ref "LED8") (pin "A") (pinfunction "A_A") (pintype "bidirectional"))
      (node (ref "R4") (pin "1") (pinfunction "1_1") (pintype "passive"))
    )
    (net (code "2") (name "+3V3_A") (class "Default")
      (node (ref "C19") (pin "1") (pinfunction "1_1") (pintype "passive"))
      (node (ref "C20") (pin "1") (pinfunction "1_1") (pintype "passive"))
      (node (ref "C22") (pin "+") (pinfunction "+_+") (pintype "passive"))
      (node (ref "C23") (pin "1") (pinfunction "1_1") (pintype "passive"))
      (node (ref "C24") (pin "1") (pinfunction "1_1") (pintype "passive"))
      (node (ref "C27") (pin "1") (pinfunction "1_1") (pintype "passive"))
      (node (ref "C28") (pin "1") (pinfunction "1_1") (pintype "passive"))
      (node (ref "C30") (pin "+") (pinfunction "+_+") (pintype "passive"))
      (node (ref "C36") (pin "1") (pinfunction "1_1") (pintype "passive"))
      (node (ref "C44") (pin "1") (pinfunction "1_1") (pintype "passive"))
      (node (ref "IC3") (pin "1") (pinfunction "VO_1") (pintype "passive"))
      (node (ref "IC4") (pin "24") (pinfunction "VDDSD_24") (pintype "power_in"))
      (node (ref "IC4") (pin "25") (pinfunction "VREFSD+_25") (pintype "power_in"))
      (node (ref "IC4") (pin "9") (pinfunction "VDDA_9") (pintype "power_in"))
      (node (ref "IC5") (pin "1") (pinfunction "CPVDD_1") (pintype "bidirectional"))
      (node (ref "IC5") (pin "8") (pinfunction "AVDD_8") (pintype "power_in"))
      (node (ref "IC6") (pin "4") (pinfunction "V+_4") (pintype "power_in"))
      (node (ref "IC7") (pin "4") (pinfunction "V+_4") (pintype "power_in"))
      (node (ref "R1") (pin "P$1") (pinfunction "E_P$1") (pintype "passive"))
      (node (ref "R2") (pin "P$1") (pinfunction "E_P$1") (pintype "passive"))
      (node (ref "R42") (pin "P$1") (pinfunction "E_P$1") (pintype "passive"))
      (node (ref "R43") (pin "P$1") (pinfunction "E_P$1") (pintype "passive"))
      (node (ref "R44") (pin "P$1") (pinfunction "E_P$1") (pintype "passive"))
      (node (ref "R7") (pin "P$1") (pinfunction "E_P$1") (pintype "passive"))
      (node (ref "R8") (pin "P$1") (pinfunction "E_P$1") (pintype "passive"))
    )
    (net (code "3") (name "ADC_FM") (class "Default")
      (node (ref "C40") (pin "2") (pinfunction "2_2") (pintype "passive"))
      (node (ref "IC4") (pin "22") (pinfunction "PE9/SDADC1_AIN7P/SDADC1_AIN8M/SDADC2_AIN7P/SDADC2_AIN8M_22") (pintype "bidirectional"))
      (node (ref "IC7") (pin "1") (pinfunction "OUT_1") (pintype "output"))
      (node (ref "R19") (pin "1") (pinfunction "1_1") (pintype "passive"))
    )
    (net (code "4") (name "ADC_GATE") (class "Default")
      (node (ref "C39") (pin "2") (pinfunction "2_2") (pintype "passive"))
      (node (ref "IC4") (pin "21") (pinfunction "PE8/SDADC1_AIN8P/SDADC2_AIN8P_21") (pintype "bidirectional"))
      (node (ref "IC6") (pin "14") (pinfunction "OUT_14") (pintype "output"))
      (node (ref "R18") (pin "1") (pinfunction "1_1") (pintype "passive"))
    )
    (net (code "5") (name "ADC_HARMONICS") (class "Default")
      (node (ref "C41") (pin "2") (pinfunction "2_2") (pintype "passive"))
      (node (ref "IC4") (pin "28") (pinfunction "PD8/SPI2_SCK/I2S2_CK/USART3_TX/SDADC3_AIN6P_28") (pintype "bidirectional"))
      (node (ref "IC7") (pin "14") (pinfunction "OUT_14") (pintype "output"))
      (node (ref "R20") (pin "1") (pinfunction "1_1") (pintype "passive"))
    )
    (net (code "6") (name "ADC_MODEL") (class "Default")
      (node (ref "C46") (pin "2") (pinfunction "2_2") (pintype "passive"))
      (node (ref "IC4") (pin "19") (pinfunction "PB1/TIM3_CH4/ADC_IN9/SDADC1_AIN5P/SDADC1_AIN6M_19") (pintype "bidirectional"))
      (node (ref "IC6") (pin "7") (pinfunction "OUT_7") (pintype "output"))
      (node (ref "R31") (pin "1") (pinfunction "1_1") (pintype "passive"))
    )
    (net (code "7") (name "ADC_MORPH") (class "Default")
      (node (ref "C49") (pin "2") (pinfunction "2_2") (pintype "passive"))
      (node (ref "IC4") (pin "27") (pinfunction "PB15/SPI2_MOSI/I2S2_SD/SDADC3_AIN7P/SDADC3_AIN8M_27") (pintype "bidirectional"))
      (node (ref "IC7") (pin "8") (pinfunction "OUT_8") (pintype "output"))
      (node (ref "R35") (pin "1") (pinfunction "1_1") (pintype "passive"))
    )
    (net (code "8") (name "ADC_TIMBRE") (class "Default")
      (node (ref "C47") (pin "2") (pinfunction "2_2") (pintype "passive"))
      (node (ref "IC4") (pin "20") (pinfunction "PB2/SDADC1_AIN4P/SDADC2_AIN6P_20") (pintype "bidirectional"))
      (node (ref "IC6") (pin "8") (pinfunction "OUT_8") (pintype "output"))
      (node (ref "R32") (pin "1") (pinfunction "1_1") (pintype "passive"))
    )
    (net (code "9") (name "ADC_TRIG") (class "Default")
      (node (ref "C38") (pin "2") (pinfunction "2_2") (pintype "passive"))
      (node (ref "IC4") (pin "18") (pinfunction "PB0/SPI1_MOSI/I2S1_SD/TIM3_CH3/ADC_IN8/SDADC1_AIN6P_18") (pintype "bidirectional"))
      (node (ref "IC6") (pin "1") (pinfunction "OUT_1") (pintype "output"))
      (node (ref "R17") (pin "1") (pinfunction "1_1") (pintype "passive"))
    )
    (net (code "10") (name "ADC_V_OCT") (class "Default")
      (node (ref "C48") (pin "2") (pinfunction "2_2") (pintype "passive"))
      (node (ref "IC4") (pin "26") (pinfunction "PB14/SPI2_MISO/I2S2_MCK/USART3_RTS/SDADC3_AIN8P_26") (pintype "bidirectional"))
      (node (ref "IC7") (pin "7") (pinfunction "OUT_7") (pintype "output"))
      (node (ref "R34") (pin "1") (pinfunction "1_1") (pintype "passive"))
    )
    (net (code "11") (name "AREF_-10") (class "Default")
      (node (ref "C50") (pin "1") (pinfunction "1_1") (pintype "passive"))
      (node (ref "IC9") (pin "2") (pinfunction "A_2") (pintype "passive"))
      (node (ref "R23") (pin "2") (pinfunction "2_2") (pintype "passive"))
      (node (ref "R25") (pin "2") (pinfunction "2_2") (pintype "passive"))
      (node (ref "R26") (pin "2") (pinfunction "2_2") (pintype "passive"))
      (node (ref "R27") (pin "2") (pinfunction "2_2") (pintype "passive"))
      (node (ref "R29") (pin "2") (pinfunction "2_2") (pintype "passive"))
      (node (ref "R30") (pin "2") (pinfunction "2_2") (pintype "passive"))
      (node (ref "R33") (pin "2") (pinfunction "2_2") (pintype "passive"))
      (node (ref "R36") (pin "2") (pinfunction "2_2") (pintype "passive"))
      (node (ref "R37") (pin "2") (pinfunction "2_2") (pintype "passive"))
    )
    (net (code "12") (name "DAC_BCK") (class "Default")
      (node (ref "IC4") (pin "29") (pinfunction "PA8/SPI2_SCK/I2S2_CK/I2C2_SMBA/USART1_CK/TIM5_CH1_29") (pintype "bidirectional"))
      (node (ref "IC5") (pin "13") (pinfunction "BCK_13") (pintype "input"))
    )
    (net (code "13") (name "DAC_DIN") (class "Default")
      (node (ref "IC4") (pin "31") (pinfunction "PA10/SPI2_MOSI/I2S2_SD/I2C2_SDA/USART1_RX/TIM2_CH4_31") (pintype "bidirectional"))
      (node (ref "IC5") (pin "14") (pinfunction "DIN_14") (pintype "input"))
    )
    (net (code "14") (name "DAC_LRCK") (class "Default")
      (node (ref "IC4") (pin "32") (pinfunction "PA11/SPI2_NSS/I2S2_WS/SPI1_NSS/I2S1_WS/USART1_CTS/CAN_RX/TIM4_CH1/TIM5_CH2_32") (pintype "bidirectional"))
      (node (ref "IC5") (pin "15") (pinfunction "LRCK_15") (pintype "input"))
    )
    (net (code "15") (name "FREQ_ATT") (class "Default")
      (node (ref "C51") (pin "1") (pinfunction "1_1") (pintype "passive"))
      (node (ref "IC4") (pin "15") (pinfunction "PA5/SPI1_SCK/I2S1_CK/TIM2_CH1/ADC_IN5/DAC1_OUT2_15") (pintype "bidirectional"))
      (node (ref "R43") (pin "P$2") (pinfunction "S_P$2") (pintype "passive"))
    )
    (net (code "16") (name "FREQ_POT") (class "Default")
      (node (ref "C11") (pin "1") (pinfunction "1_1") (pintype "passive"))
      (node (ref "IC4") (pin "10") (pinfunction "PA0/USART2_CTS/TIM2_CH1/TIM5_CH1/ADC_IN0_10") (pintype "bidirectional"))
      (node (ref "R1") (pin "P$2") (pinfunction "S_P$2") (pintype "passive"))
    )
    (net (code "17") (name "GND") (class "Default")
      (node (ref "C1") (pin "2") (pinfunction "2_2") (pintype "passive"))
      (node (ref "C10") (pin "2") (pinfunction "2_2") (pintype "passive"))
      (node (ref "C11") (pin "2") (pinfunction "2_2") (pintype "passive"))
      (node (ref "C12") (pin "2") (pinfunction "2_2") (pintype "passive"))
      (node (ref "C13") (pin "2") (pinfunction "2_2") (pintype "passive"))
      (node (ref "C14") (pin "1") (pinfunction "1_1") (pintype "passive"))
      (node (ref "C15") (pin "2") (pinfunction "2_2") (pintype "passive"))
      (node (ref "C16") (pin "-") (pinfunction "-_-") (pintype "passive"))
      (node (ref "C17") (pin "2") (pinfunction "2_2") (pintype "passive"))
      (node (ref "C18") (pin "2") (pinfunction "2_2") (pintype "passive"))
      (node (ref "C19") (pin "2") (pinfunction "2_2") (pintype "passive"))
      (node (ref "C2") (pin "2") (pinfunction "2_2") (pintype "passive"))
      (node (ref "C20") (pin "2") (pinfunction "2_2") (pintype "passive"))
      (node (ref "C21") (pin "1") (pinfunction "1_1") (pintype "passive"))
      (node (ref "C22") (pin "-") (pinfunction "-_-") (pintype "passive"))
      (node (ref "C23") (pin "2") (pinfunction "2_2") (pintype "passive"))
      (node (ref "C24") (pin "2") (pinfunction "2_2") (pintype "passive"))
      (node (ref "C25") (pin "2") (pinfunction "2_2") (pintype "passive"))
      (node (ref "C26") (pin "2") (pinfunction "2_2") (pintype "passive"))
      (node (ref "C27") (pin "2") (pinfunction "2_2") (pintype "passive"))
      (node (ref "C28") (pin "2") (pinfunction "2_2") (pintype "passive"))
      (node (ref "C3") (pin "-") (pinfunction "-_-") (pintype "passive"))
      (node (ref "C30") (pin "-") (pinfunction "-_-") (pintype "passive"))
      (node (ref "C31") (pin "2") (pinfunction "2_2") (pintype "passive"))
      (node (ref "C32") (pin "2") (pinfunction "2_2") (pintype "passive"))
      (node (ref "C33") (pin "2") (pinfunction "2_2") (pintype "passive"))
      (node (ref "C34") (pin "2") (pinfunction "2_2") (pintype "passive"))
      (node (ref "C35") (pin "2") (pinfunction "2_2") (pintype "passive"))
      (node (ref "C36") (pin "2") (pinfunction "2_2") (pintype "passive"))
      (node (ref "C37") (pin "2") (pinfunction "2_2") (pintype "passive"))
      (node (ref "C4") (pin "-") (pinfunction "-_-") (pintype "passive"))
      (node (ref "C44") (pin "2") (pinfunction "2_2") (pintype "passive"))
      (node (ref "C45") (pin "1") (pinfunction "1_1") (pintype "passive"))
      (node (ref "C5") (pin "+") (pinfunction "+_+") (pintype "passive"))
      (node (ref "C50") (pin "2") (pinfunction "2_2") (pintype "passive"))
      (node (ref "C51") (pin "2") (pinfunction "2_2") (pintype "passive"))
      (node (ref "C52") (pin "2") (pinfunction "2_2") (pintype "passive"))
      (node (ref "C53") (pin "2") (pinfunction "2_2") (pintype "passive"))
      (node (ref "C54") (pin "2") (pinfunction "2_2") (pintype "passive"))
      (node (ref "C55") (pin "2") (pinfunction "2_2") (pintype "passive"))
      (node (ref "C56") (pin "2") (pinfunction "2_2") (pintype "passive"))
      (node (ref "C57") (pin "2") (pinfunction "2_2") (pintype "passive"))
      (node (ref "C58") (pin "2") (pinfunction "2_2") (pintype "passive"))
      (node (ref "C59") (pin "2") (pinfunction "2_2") (pintype "passive"))
      (node (ref "C6") (pin "2") (pinfunction "2_2") (pintype "passive"))
      (node (ref "C60") (pin "2") (pinfunction "2_2") (pintype "passive"))
      (node (ref "C61") (pin "2") (pinfunction "2_2") (pintype "passive"))
      (node (ref "C7") (pin "-") (pinfunction "-_-") (pintype "passive"))
      (node (ref "C8") (pin "2") (pinfunction "2_2") (pintype "passive"))
      (node (ref "C9") (pin "2") (pinfunction "2_2") (pintype "passive"))
      (node (ref "D3") (pin "1") (pinfunction "A_1") (pintype "passive"))
      (node (ref "IC1") (pin "2") (pinfunction "GND_2") (pintype "passive"))
      (node (ref "IC2") (pin "1") (pinfunction "GND_1") (pintype "bidirectional"))
      (node (ref "IC2") (pin "21") (pinfunction "BLANK_21") (pintype "bidirectional"))
      (node (ref "IC3") (pin "2") (pinfunction "GND_2") (pintype "passive"))
      (node (ref "IC4") (pin "23") (pinfunction "VSSSD/VREFSD-_23") (pintype "power_in"))
      (node (ref "IC4") (pin "44") (pinfunction "BOOT0_44") (pintype "bidirectional"))
      (node (ref "IC4") (pin "47") (pinfunction "VSS_1_47") (pintype "power_in"))
      (node (ref "IC4") (pin "8") (pinfunction "VSSA_8") (pintype "power_in"))
      (node (ref "IC5") (pin "10") (pinfunction "DEMP_10") (pintype "input"))
      (node (ref "IC5") (pin "12") (pinfunction "SCK_12") (pintype "input"))
      (node (ref "IC5") (pin "16") (pinfunction "FMT_16") (pintype "input"))
      (node (ref "IC5") (pin "19") (pinfunction "DGND_19") (pintype "power_in"))
      (node (ref "IC5") (pin "3") (pinfunction "CPGND_3") (pintype "bidirectional"))
      (node (ref "IC5") (pin "9") (pinfunction "AGND_9") (pintype "power_in"))
      (node (ref "IC6") (pin "10") (pinfunction "+IN_10") (pintype "input"))
      (node (ref "IC6") (pin "11") (pinfunction "V-_11") (pintype "power_in"))
      (node (ref "IC6") (pin "12") (pinfunction "+IN_12") (pintype "input"))
      (node (ref "IC6") (pin "3") (pinfunction "+IN_3") (pintype "input"))
      (node (ref "IC6") (pin "5") (pinfunction "+IN_5") (pintype "input"))
      (node (ref "IC7") (pin "10") (pinfunction "+IN_10") (pintype "input"))
      (node (ref "IC7") (pin "11") (pinfunction "V-_11") (pintype "power_in"))
      (node (ref "IC7") (pin "12") (pinfunction "+IN_12") (pintype "input"))
      (node (ref "IC7") (pin "3") (pinfunction "+IN_3") (pintype "input"))
      (node (ref "IC7") (pin "5") (pinfunction "+IN_5") (pintype "input"))
      (node (ref "IC8") (pin "3") (pinfunction "+IN_3") (pintype "input"))
      (node (ref "IC8") (pin "5") (pinfunction "+IN_5") (pintype "input"))
      (node (ref "IC9") (pin "1") (pinfunction "C_1") (pintype "passive"))
      (node (ref "J1") (pin "P1") (pinfunction "1_P1") (pintype "passive"))
      (node (ref "J1") (pin "P2") (pinfunction "2_P2") (pintype "passive"))
      (node (ref "J10") (pin "P1") (pinfunction "1_P1") (pintype "passive"))
      (node (ref "J2") (pin "P1") (pinfunction "1_P1") (pintype "passive"))
      (node (ref "J3") (pin "P1") (pinfunction "1_P1") (pintype "passive"))
      (node (ref "J4") (pin "P1") (pinfunction "1_P1") (pintype "passive"))
      (node (ref "J5") (pin "P1") (pinfunction "1_P1") (pintype "passive"))
      (node (ref "J5") (pin "P2") (pinfunction "2_P2") (pintype "passive"))
      (node (ref "J6") (pin "P1") (pinfunction "1_P1") (pintype "passive"))
      (node (ref "J7") (pin "P1") (pinfunction "1_P1") (pintype "passive"))
      (node (ref "J8") (pin "P1") (pinfunction "1_P1") (pintype "passive"))
      (node (ref "J8") (pin "P2") (pinfunction "2_P2") (pintype "passive"))
      (node (ref "J9") (pin "P1") (pinfunction "1_P1") (pintype "passive"))
      (node (ref "JP6") (pin "1") (pinfunction "1_1") (pintype "passive"))
      (node (ref "JP8") (pin "3") (pinfunction "3_3") (pintype "passive"))
      (node (ref "JP8") (pin "4") (pinfunction "4_4") (pintype "passive"))
      (node (ref "JP8") (pin "5") (pinfunction "5_5") (pintype "passive"))
      (node (ref "JP8") (pin "6") (pinfunction "6_6") (pintype "passive"))
      (node (ref "JP8") (pin "7") (pinfunction "7_7") (pintype "passive"))
      (node (ref "JP8") (pin "8") (pinfunction "8_8") (pintype "passive"))
      (node (ref "Q1") (pin "2") (pinfunction "LID1_2") (pintype "power_in"))
      (node (ref "Q1") (pin "4") (pinfunction "LID2_4") (pintype "power_in"))
      (node (ref "R1") (pin "P$3") (pinfunction "A_P$3") (pintype "passive"))
      (node (ref "R2") (pin "P$3") (pinfunction "A_P$3") (pintype "passive"))
      (node (ref "R3") (pin "2") (pinfunction "2_2") (pintype "passive"))
      (node (ref "R42") (pin "P$3") (pinfunction "A_P$3") (pintype "passive"))
      (node (ref "R43") (pin "P$3") (pinfunction "A_P$3") (pintype "passive"))
      (node (ref "R44") (pin "P$3") (pinfunction "A_P$3") (pintype "passive"))
      (node (ref "R7") (pin "P$3") (pinfunction "A_P$3") (pintype "passive"))
      (node (ref "R8") (pin "P$3") (pinfunction "A_P$3") (pintype "passive"))
      (node (ref "SW1") (pin "1") (pinfunction "1_1") (pintype "passive"))
      (node (ref "SW1") (pin "2") (pinfunction "2_2") (pintype "passive"))
      (node (ref "SW2") (pin "1") (pinfunction "1_1") (pintype "passive"))
      (node (ref "SW2") (pin "2") (pinfunction "2_2") (pintype "passive"))
    )
    (net (code "18") (name "HARMONICS_POT") (class "Default")
      (node (ref "C12") (pin "1") (pinfunction "1_1") (pintype "passive"))
      (node (ref "IC4") (pin "12") (pinfunction "PA2/SPI3_MISO/I2S3_MCK/USART2_TX/TIM2_CH3/TIM5_CH3/ADC_IN2_12") (pintype "bidirectional"))
      (node (ref "R2") (pin "P$2") (pinfunction "S_P$2") (pintype "passive"))
    )
    (net (code "19") (name "LEDS_SCK") (class "Default")
      (node (ref "IC2") (pin "3") (pinfunction "SCLK_3") (pintype "bidirectional"))
      (node (ref "IC4") (pin "33") (pinfunction "PA12/SPI1_SCK/I2S1_CK/USART1_RTS/CAN_TX/TIM4_CH2/TIM5_CH3_33") (pintype "bidirectional"))
    )
    (net (code "20") (name "LEDS_SIN") (class "Default")
      (node (ref "IC2") (pin "2") (pinfunction "SIN_2") (pintype "bidirectional"))
      (node (ref "IC4") (pin "35") (pinfunction "PF6/SPI1_MOSI/I2S1_SD/USART3_RTS/TIM4_CH4/I2C2_SCL_35") (pintype "bidirectional"))
    )
    (net (code "21") (name "LEDS_SS") (class "Default")
      (node (ref "IC2") (pin "4") (pinfunction "LAT_4") (pintype "bidirectional"))
      (node (ref "IC4") (pin "36") (pinfunction "PF7/I2C2_SDA/USART2_CK_36") (pintype "bidirectional"))
    )
    (net (code "22") (name "MORPH_ATT") (class "Default")
      (node (ref "C52") (pin "1") (pinfunction "1_1") (pintype "passive"))
      (node (ref "IC4") (pin "14") (pinfunction "PA4/SPI1_NSS/I2S1_WS/SPI3_NSS/I2S3_WS/USART2_CK/TIM3_CH2/ADC_IN4/DAC1_OUT1_14") (pintype "bidirectional"))
      (node (ref "R44") (pin "P$2") (pinfunction "S_P$2") (pintype "passive"))
    )
    (net (code "23") (name "MORPH_POT") (class "Default")
      (node (ref "C34") (pin "1") (pinfunction "1_1") (pintype "passive"))
      (node (ref "IC4") (pin "11") (pinfunction "PA1/SPI3_SCK/I2S3_CK/USART2_RTS/TIM2_CH2/TIM5_CH2/ADC_IN1_11") (pintype "bidirectional"))
      (node (ref "R8") (pin "P$2") (pinfunction "S_P$2") (pintype "passive"))
    )
    (net (code "24") (name "NORMALIZATION_PROBE") (class "Default")
      (node (ref "D3") (pin "3") (pinfunction "AC_3") (pintype "passive"))
      (node (ref "IC4") (pin "30") (pinfunction "PA9/SPI_MISO/I2S2_MCK/I2C2_SCL/USART1_TX/TIM2_CH3_30") (pintype "bidirectional"))
      (node (ref "R45") (pin "2") (pinfunction "2_2") (pintype "passive"))
      (node (ref "R48") (pin "2") (pinfunction "2_2") (pintype "passive"))
      (node (ref "R49") (pin "2") (pinfunction "2_2") (pintype "passive"))
      (node (ref "R50") (pin "1") (pinfunction "1_1") (pintype "passive"))
      (node (ref "R51") (pin "2") (pinfunction "2_2") (pintype "passive"))
    )
    (net (code "25") (name "Net-(C2-Pad1)") (class "Default")
      (node (ref "C2") (pin "1") (pinfunction "1_1") (pintype "passive"))
      (node (ref "D1") (pin "C") (pinfunction "C_C") (pintype "passive"))
      (node (ref "L1") (pin "1") (pinfunction "1_1") (pintype "passive"))
      (node (ref "L2") (pin "2") (pinfunction "2_2") (pintype "passive"))
      (node (ref "L5") (pin "2") (pinfunction "2_2") (pintype "passive"))
    )
    (net (code "26") (name "Net-(C21-Pad2)") (class "Default")
      (node (ref "C21") (pin "2") (pinfunction "2_2") (pintype "passive"))
      (node (ref "Q1") (pin "1") (pinfunction "1_1") (pintype "passive"))
      (node (ref "R6") (pin "2") (pinfunction "2_2") (pintype "passive"))
    )
    (net (code "27") (name "Net-(C33-Pad1)") (class "Default")
      (node (ref "C33") (pin "1") (pinfunction "1_1") (pintype "passive"))
      (node (ref "R11") (pin "1") (pinfunction "1_1") (pintype "passive"))
      (node (ref "R21") (pin "2") (pinfunction "2_2") (pintype "passive"))
    )
    (net (code "28") (name "Net-(C35-Pad1)") (class "Default")
      (node (ref "C35") (pin "1") (pinfunction "1_1") (pintype "passive"))
      (node (ref "R12") (pin "1") (pinfunction "1_1") (pintype "passive"))
      (node (ref "R16") (pin "2") (pinfunction "2_2") (pintype "passive"))
    )
    (net (code "29") (name "Net-(D1-PadA)") (class "Default")
      (node (ref "D1") (pin "A") (pinfunction "A_A") (pintype "passive"))
      (node (ref "JP8") (pin "10") (pinfunction "10_10") (pintype "passive"))
      (node (ref "JP8") (pin "9") (pinfunction "9_9") (pintype "passive"))
    )
    (net (code "30") (name "Net-(D2-PadA)") (class "Default")
      (node (ref "D2") (pin "A") (pinfunction "A_A") (pintype "passive"))
      (node (ref "L3") (pin "2") (pinfunction "2_2") (pintype "passive"))
    )
    (net (code "31") (name "Net-(D2-PadC)") (class "Default")
      (node (ref "D2") (pin "C") (pinfunction "C_C") (pintype "passive"))
      (node (ref "JP8") (pin "1") (pinfunction "1_1") (pintype "passive"))
      (node (ref "JP8") (pin "2") (pinfunction "2_2") (pintype "passive"))
    )
    (net (code "32") (name "Net-(IC1-VI)") (class "Default")
      (node (ref "C1") (pin "1") (pinfunction "1_1") (pintype "passive"))
      (node (ref "IC1") (pin "1") (pinfunction "VI_1") (pintype "input"))
      (node (ref "L1") (pin "2") (pinfunction "2_2") (pintype "passive"))
    )
    (net (code "33") (name "Net-(IC2-IREF)") (class "Default")
      (node (ref "IC2") (pin "23") (pinfunction "IREF_23") (pintype "bidirectional"))
      (node (ref "R3") (pin "1") (pinfunction "1_1") (pintype "passive"))
    )
    (net (code "34") (name "Net-(IC2-OUT0)") (class "Default")
      (node (ref "IC2") (pin "5") (pinfunction "OUT0_5") (pintype "bidirectional"))
      (node (ref "LED5") (pin "RED_C") (pinfunction "RED_RED_C") (pintype "bidirectional"))
    )
    (net (code "35") (name "Net-(IC2-OUT1)") (class "Default")
      (node (ref "IC2") (pin "6") (pinfunction "OUT1_6") (pintype "bidirectional"))
      (node (ref "LED5") (pin "GREEN_C") (pinfunction "GRN_GREEN_C") (pintype "bidirectional"))
    )
    (net (code "36") (name "Net-(IC2-OUT2)") (class "Default")
      (node (ref "IC2") (pin "7") (pinfunction "OUT2_7") (pintype "bidirectional"))
      (node (ref "LED6") (pin "RED_C") (pinfunction "RED_RED_C") (pintype "bidirectional"))
    )
    (net (code "37") (name "Net-(IC2-OUT3)") (class "Default")
      (node (ref "IC2") (pin "8") (pinfunction "OUT3_8") (pintype "bidirectional"))
      (node (ref "LED6") (pin "GREEN_C") (pinfunction "GRN_GREEN_C") (pintype "bidirectional"))
    )
    (net (code "38") (name "Net-(IC2-OUT4)") (class "Default")
      (node (ref "IC2") (pin "9") (pinfunction "OUT4_9") (pintype "bidirectional"))
      (node (ref "LED7") (pin "RED_C") (pinfunction "RED_RED_C") (pintype "bidirectional"))
    )
    (net (code "39") (name "Net-(IC2-OUT5)") (class "Default")
      (node (ref "IC2") (pin "10") (pinfunction "OUT5_10") (pintype "bidirectional"))
      (node (ref "LED7") (pin "GREEN_C") (pinfunction "GRN_GREEN_C") (pintype "bidirectional"))
    )
    (net (code "40") (name "Net-(IC2-OUT6)") (class "Default")
      (node (ref "IC2") (pin "11") (pinfunction "OUT6_11") (pintype "bidirectional"))
      (node (ref "LED8") (pin "RED_C") (pinfunction "RED_RED_C") (pintype "bidirectional"))
    )
    (net (code "41") (name "Net-(IC2-OUT7)") (class "Default")
      (node (ref "IC2") (pin "12") (pinfunction "OUT7_12") (pintype "bidirectional"))
      (node (ref "LED8") (pin "GREEN_C") (pinfunction "GRN_GREEN_C") (pintype "bidirectional"))
    )
    (net (code "42") (name "Net-(IC2-OUT8)") (class "Default")
      (node (ref "IC2") (pin "13") (pinfunction "OUT8_13") (pintype "bidirectional"))
      (node (ref "LED4") (pin "RED_C") (pinfunction "RED_RED_C") (pintype "bidirectional"))
    )
    (net (code "43") (name "Net-(IC2-OUT9)") (class "Default")
      (node (ref "IC2") (pin "14") (pinfunction "OUT9_14") (pintype "bidirectional"))
      (node (ref "LED4") (pin "GREEN_C") (pinfunction "GRN_GREEN_C") (pintype "bidirectional"))
    )
    (net (code "44") (name "Net-(IC2-OUT10)") (class "Default")
      (node (ref "IC2") (pin "15") (pinfunction "OUT10_15") (pintype "bidirectional"))
      (node (ref "LED3") (pin "RED_C") (pinfunction "RED_RED_C") (pintype "bidirectional"))
    )
    (net (code "45") (name "Net-(IC2-OUT11)") (class "Default")
      (node (ref "IC2") (pin "16") (pinfunction "OUT11_16") (pintype "bidirectional"))
      (node (ref "LED3") (pin "GREEN_C") (pinfunction "GRN_GREEN_C") (pintype "bidirectional"))
    )
    (net (code "46") (name "Net-(IC2-OUT12)") (class "Default")
      (node (ref "IC2") (pin "17") (pinfunction "OUT12_17") (pintype "bidirectional"))
      (node (ref "LED2") (pin "RED_C") (pinfunction "RED_RED_C") (pintype "bidirectional"))
    )
    (net (code "47") (name "Net-(IC2-OUT13)") (class "Default")
      (node (ref "IC2") (pin "18") (pinfunction "OUT13_18") (pintype "bidirectional"))
      (node (ref "LED2") (pin "GREEN_C") (pinfunction "GRN_GREEN_C") (pintype "bidirectional"))
    )
    (net (code "48") (name "Net-(IC2-OUT14)") (class "Default")
      (node (ref "IC2") (pin "19") (pinfunction "OUT14_19") (pintype "bidirectional"))
      (node (ref "LED1") (pin "RED_C") (pinfunction "RED_RED_C") (pintype "bidirectional"))
    )
    (net (code "49") (name "Net-(IC2-OUT15)") (class "Default")
      (node (ref "IC2") (pin "20") (pinfunction "OUT15_20") (pintype "bidirectional"))
      (node (ref "LED1") (pin "GREEN_C") (pinfunction "GRN_GREEN_C") (pintype "bidirectional"))
    )
    (net (code "50") (name "Net-(IC2-VCC)") (class "Default")
      (node (ref "C7") (pin "+") (pinfunction "+_+") (pintype "passive"))
      (node (ref "C8") (pin "1") (pinfunction "1_1") (pintype "passive"))
      (node (ref "IC2") (pin "24") (pinfunction "VCC_24") (pintype "bidirectional"))
      (node (ref "L4") (pin "1") (pinfunction "1_1") (pintype "passive"))
    )
    (net (code "51") (name "Net-(IC3-VI)") (class "Default")
      (node (ref "C13") (pin "1") (pinfunction "1_1") (pintype "passive"))
      (node (ref "IC3") (pin "3") (pinfunction "VI_3") (pintype "input"))
      (node (ref "L5") (pin "1") (pinfunction "1_1") (pintype "passive"))
    )
    (net (code "52") (name "Net-(IC4-PF0{slash}OSC_IN{slash}I2C2_SDA)") (class "Default")
      (node (ref "IC4") (pin "5") (pinfunction "PF0/OSC_IN/I2C2_SDA_5") (pintype "bidirectional"))
      (node (ref "R5") (pin "1") (pinfunction "1_1") (pintype "passive"))
    )
    (net (code "53") (name "Net-(IC4-PF1{slash}OSC_OUT{slash}I2C2_SCL)") (class "Default")
      (node (ref "IC4") (pin "6") (pinfunction "PF1/OSC_OUT/I2C2_SCL_6") (pintype "bidirectional"))
      (node (ref "R6") (pin "1") (pinfunction "1_1") (pintype "passive"))
    )
    (net (code "54") (name "Net-(IC5-CAPM)") (class "Default")
      (node (ref "C29") (pin "2") (pinfunction "2_2") (pintype "passive"))
      (node (ref "IC5") (pin "4") (pinfunction "CAPM_4") (pintype "bidirectional"))
    )
    (net (code "55") (name "Net-(IC5-CAPP)") (class "Default")
      (node (ref "C29") (pin "1") (pinfunction "1_1") (pintype "passive"))
      (node (ref "IC5") (pin "2") (pinfunction "CAPP_2") (pintype "bidirectional"))
    )
    (net (code "56") (name "Net-(IC5-LDOO)") (class "Default")
      (node (ref "C18") (pin "1") (pinfunction "1_1") (pintype "passive"))
      (node (ref "IC5") (pin "18") (pinfunction "LDOO_18") (pintype "bidirectional"))
    )
    (net (code "57") (name "Net-(IC5-OUTL)") (class "Default")
      (node (ref "IC5") (pin "6") (pinfunction "OUTL_6") (pintype "output"))
      (node (ref "R11") (pin "2") (pinfunction "2_2") (pintype "passive"))
    )
    (net (code "58") (name "Net-(IC5-OUTR)") (class "Default")
      (node (ref "IC5") (pin "7") (pinfunction "OUTR_7") (pintype "output"))
      (node (ref "R12") (pin "2") (pinfunction "2_2") (pintype "passive"))
    )
    (net (code "59") (name "Net-(IC5-VNEG)") (class "Default")
      (node (ref "C31") (pin "1") (pinfunction "1_1") (pintype "passive"))
      (node (ref "IC5") (pin "5") (pinfunction "VNEG_5") (pintype "input"))
    )
    (net (code "60") (name "Net-(IC6A--IN)") (class "Default")
      (node (ref "C38") (pin "1") (pinfunction "1_1") (pintype "passive"))
      (node (ref "IC6") (pin "2") (pinfunction "-IN_2") (pintype "input"))
      (node (ref "R17") (pin "2") (pinfunction "2_2") (pintype "passive"))
      (node (ref "R24") (pin "1") (pinfunction "1_1") (pintype "passive"))
      (node (ref "R25") (pin "1") (pinfunction "1_1") (pintype "passive"))
    )
    (net (code "61") (name "Net-(IC6B--IN)") (class "Default")
      (node (ref "C46") (pin "1") (pinfunction "1_1") (pintype "passive"))
      (node (ref "IC6") (pin "6") (pinfunction "-IN_6") (pintype "input"))
      (node (ref "R30") (pin "1") (pinfunction "1_1") (pintype "passive"))
      (node (ref "R31") (pin "2") (pinfunction "2_2") (pintype "passive"))
      (node (ref "R40") (pin "1") (pinfunction "1_1") (pintype "passive"))
    )
    (net (code "62") (name "Net-(IC6C--IN)") (class "Default")
      (node (ref "C47") (pin "1") (pinfunction "1_1") (pintype "passive"))
      (node (ref "IC6") (pin "9") (pinfunction "-IN_9") (pintype "input"))
      (node (ref "R32") (pin "2") (pinfunction "2_2") (pintype "passive"))
      (node (ref "R33") (pin "1") (pinfunction "1_1") (pintype "passive"))
      (node (ref "R41") (pin "1") (pinfunction "1_1") (pintype "passive"))
    )
    (net (code "63") (name "Net-(IC6D--IN)") (class "Default")
      (node (ref "C39") (pin "1") (pinfunction "1_1") (pintype "passive"))
      (node (ref "IC6") (pin "13") (pinfunction "-IN_13") (pintype "input"))
      (node (ref "R14") (pin "1") (pinfunction "1_1") (pintype "passive"))
      (node (ref "R18") (pin "2") (pinfunction "2_2") (pintype "passive"))
      (node (ref "R26") (pin "1") (pinfunction "1_1") (pintype "passive"))
    )
    (net (code "64") (name "Net-(IC7A--IN)") (class "Default")
      (node (ref "C40") (pin "1") (pinfunction "1_1") (pintype "passive"))
      (node (ref "IC7") (pin "2") (pinfunction "-IN_2") (pintype "input"))
      (node (ref "R15") (pin "1") (pinfunction "1_1") (pintype "passive"))
      (node (ref "R19") (pin "2") (pinfunction "2_2") (pintype "passive"))
      (node (ref "R23") (pin "1") (pinfunction "1_1") (pintype "passive"))
    )
    (net (code "65") (name "Net-(IC7B--IN)") (class "Default")
      (node (ref "C48") (pin "1") (pinfunction "1_1") (pintype "passive"))
      (node (ref "IC7") (pin "6") (pinfunction "-IN_6") (pintype "input"))
      (node (ref "R29") (pin "1") (pinfunction "1_1") (pintype "passive"))
      (node (ref "R34") (pin "2") (pinfunction "2_2") (pintype "passive"))
      (node (ref "R38") (pin "1") (pinfunction "1_1") (pintype "passive"))
    )
    (net (code "66") (name "Net-(IC7C--IN)") (class "Default")
      (node (ref "C49") (pin "1") (pinfunction "1_1") (pintype "passive"))
      (node (ref "IC7") (pin "9") (pinfunction "-IN_9") (pintype "input"))
      (node (ref "R35") (pin "2") (pinfunction "2_2") (pintype "passive"))
      (node (ref "R36") (pin "1") (pinfunction "1_1") (pintype "passive"))
      (node (ref "R39") (pin "1") (pinfunction "1_1") (pintype "passive"))
    )
    (net (code "67") (name "Net-(IC7D--IN)") (class "Default")
      (node (ref "C41") (pin "1") (pinfunction "1_1") (pintype "passive"))
      (node (ref "IC7") (pin "13") (pinfunction "-IN_13") (pintype "input"))
      (node (ref "R13") (pin "1") (pinfunction "1_1") (pintype "passive"))
      (node (ref "R20") (pin "2") (pinfunction "2_2") (pintype "passive"))
      (node (ref "R27") (pin "1") (pinfunction "1_1") (pintype "passive"))
    )
    (net (code "68") (name "Net-(IC8A--IN)") (class "Default")
      (node (ref "C42") (pin "1") (pinfunction "1_1") (pintype "passive"))
      (node (ref "IC8") (pin "2") (pinfunction "-IN_2") (pintype "input"))
      (node (ref "R21") (pin "1") (pinfunction "1_1") (pintype "passive"))
      (node (ref "R22") (pin "2") (pinfunction "2_2") (pintype "passive"))
    )
    (net (code "69") (name "Net-(IC8A-OUT)") (class "Default")
      (node (ref "C42") (pin "2") (pinfunction "2_2") (pintype "passive"))
      (node (ref "IC8") (pin "1") (pinfunction "OUT_1") (pintype "output"))
      (node (ref "R22") (pin "1") (pinfunction "1_1") (pintype "passive"))
      (node (ref "R46") (pin "2") (pinfunction "2_2") (pintype "passive"))
    )
    (net (code "70") (name "Net-(IC8B--IN)") (class "Default")
      (node (ref "C43") (pin "1") (pinfunction "1_1") (pintype "passive"))
      (node (ref "IC8") (pin "6") (pinfunction "-IN_6") (pintype "input"))
      (node (ref "R16") (pin "1") (pinfunction "1_1") (pintype "passive"))
      (node (ref "R28") (pin "2") (pinfunction "2_2") (pintype "passive"))
    )
    (net (code "71") (name "Net-(IC8B-OUT)") (class "Default")
      (node (ref "C43") (pin "2") (pinfunction "2_2") (pintype "passive"))
      (node (ref "IC8") (pin "7") (pinfunction "OUT_7") (pintype "output"))
      (node (ref "R28") (pin "1") (pinfunction "1_1") (pintype "passive"))
      (node (ref "R47") (pin "2") (pinfunction "2_2") (pintype "passive"))
    )
    (net (code "72") (name "Net-(J1-3)") (class "Default")
      (node (ref "C55") (pin "1") (pinfunction "1_1") (pintype "passive"))
      (node (ref "J1") (pin "P3") (pinfunction "3_P3") (pintype "passive"))
      (node (ref "R40") (pin "2") (pinfunction "2_2") (pintype "passive"))
    )
    (net (code "73") (name "Net-(J2-2)") (class "Default")
      (node (ref "J2") (pin "P2") (pinfunction "2_P2") (pintype "passive"))
      (node (ref "R48") (pin "1") (pinfunction "1_1") (pintype "passive"))
    )
    (net (code "74") (name "Net-(J2-3)") (class "Default")
      (node (ref "C56") (pin "1") (pinfunction "1_1") (pintype "passive"))
      (node (ref "J2") (pin "P3") (pinfunction "3_P3") (pintype "passive"))
      (node (ref "R41") (pin "2") (pinfunction "2_2") (pintype "passive"))
    )
    (net (code "75") (name "Net-(J3-2)") (class "Default")
      (node (ref "J3") (pin "P2") (pinfunction "2_P2") (pintype "passive"))
      (node (ref "R49") (pin "1") (pinfunction "1_1") (pintype "passive"))
    )
    (net (code "76") (name "Net-(J3-3)") (class "Default")
      (node (ref "C57") (pin "1") (pinfunction "1_1") (pintype "passive"))
      (node (ref "J3") (pin "P3") (pinfunction "3_P3") (pintype "passive"))
      (node (ref "R15") (pin "2") (pinfunction "2_2") (pintype "passive"))
    )
    (net (code "77") (name "Net-(J4-2)") (class "Default")
      (node (ref "J4") (pin "P2") (pinfunction "2_P2") (pintype "passive"))
      (node (ref "R45") (pin "1") (pinfunction "1_1") (pintype "passive"))
    )
    (net (code "78") (name "Net-(J4-3)") (class "Default")
      (node (ref "C54") (pin "1") (pinfunction "1_1") (pintype "passive"))
      (node (ref "J4") (pin "P3") (pinfunction "3_P3") (pintype "passive"))
      (node (ref "R39") (pin "2") (pinfunction "2_2") (pintype "passive"))
    )
    (net (code "79") (name "Net-(J5-3)") (class "Default")
      (node (ref "C58") (pin "1") (pinfunction "1_1") (pintype "passive"))
      (node (ref "J5") (pin "P3") (pinfunction "3_P3") (pintype "passive"))
      (node (ref "R13") (pin "2") (pinfunction "2_2") (pintype "passive"))
    )
    (net (code "80") (name "Net-(J6-2)") (class "Default")
      (node (ref "J6") (pin "P2") (pinfunction "2_P2") (pintype "passive"))
      (node (ref "R50") (pin "2") (pinfunction "2_2") (pintype "passive"))
    )
    (net (code "81") (name "Net-(J6-3)") (class "Default")
      (node (ref "C59") (pin "1") (pinfunction "1_1") (pintype "passive"))
      (node (ref "J6") (pin "P3") (pinfunction "3_P3") (pintype "passive"))
      (node (ref "R24") (pin "2") (pinfunction "2_2") (pintype "passive"))
    )
    (net (code "82") (name "Net-(J7-2)") (class "Default")
      (node (ref "J7") (pin "P2") (pinfunction "2_P2") (pintype "passive"))
      (node (ref "R51") (pin "1") (pinfunction "1_1") (pintype "passive"))
    )
    (net (code "83") (name "Net-(J7-3)") (class "Default")
      (node (ref "C61") (pin "1") (pinfunction "1_1") (pintype "passive"))
      (node (ref "J7") (pin "P3") (pinfunction "3_P3") (pintype "passive"))
      (node (ref "R14") (pin "2") (pinfunction "2_2") (pintype "passive"))
    )
    (net (code "84") (name "Net-(J8-3)") (class "Default")
      (node (ref "C60") (pin "1") (pinfunction "1_1") (pintype "passive"))
      (node (ref "J8") (pin "P3") (pinfunction "3_P3") (pintype "passive"))
      (node (ref "R38") (pin "2") (pinfunction "2_2") (pintype "passive"))
    )
    (net (code "85") (name "Net-(J9-3)") (class "Default")
      (node (ref "J9") (pin "P3") (pinfunction "3_P3") (pintype "passive"))
      (node (ref "R46") (pin "1") (pinfunction "1_1") (pintype "passive"))
    )
    (net (code "86") (name "Net-(J10-3)") (class "Default")
      (node (ref "J10") (pin "P3") (pinfunction "3_P3") (pintype "passive"))
      (node (ref "R47") (pin "1") (pinfunction "1_1") (pintype "passive"))
    )
    (net (code "87") (name "Net-(JP5-Pad1)") (class "Default")
      (node (ref "JP5") (pin "1") (pinfunction "1_1") (pintype "passive"))
      (node (ref "R9") (pin "1") (pinfunction "1_1") (pintype "passive"))
    )
    (net (code "88") (name "Net-(JP5-Pad2)") (class "Default")
      (node (ref "JP5") (pin "2") (pinfunction "2_2") (pintype "passive"))
      (node (ref "R10") (pin "1") (pinfunction "1_1") (pintype "passive"))
    )
    (net (code "89") (name "Net-(Q1B-2)") (class "Default")
      (node (ref "C14") (pin "2") (pinfunction "2_2") (pintype "passive"))
      (node (ref "Q1") (pin "3") (pinfunction "2_3") (pintype "passive"))
      (node (ref "R5") (pin "2") (pinfunction "2_2") (pintype "passive"))
    )
    (net (code "90") (name "RESET") (class "Default")
      (node (ref "C15") (pin "1") (pinfunction "1_1") (pintype "passive"))
      (node (ref "IC4") (pin "7") (pinfunction "NRST_7") (pintype "bidirectional"))
      (node (ref "JP6") (pin "4") (pinfunction "4_4") (pintype "passive"))
      (node (ref "R4") (pin "2") (pinfunction "2_2") (pintype "passive"))
    )
    (net (code "91") (name "RX") (class "Default")
      (node (ref "IC4") (pin "46") (pinfunction "PB9/SPI2_NSS/I2S2_WS/I2C1_SDA/USART3_RX/CAN_TX/TIM4_CH4_46") (pintype "bidirectional"))
      (node (ref "R9") (pin "2") (pinfunction "2_2") (pintype "passive"))
    )
    (net (code "92") (name "SWCLK") (class "Default")
      (node (ref "IC4") (pin "37") (pinfunction "PA14/I2C1_SDA/JTCK-SWCLK_37") (pintype "bidirectional"))
      (node (ref "JP6") (pin "3") (pinfunction "3_3") (pintype "passive"))
    )
    (net (code "93") (name "SWDIO") (class "Default")
      (node (ref "IC4") (pin "34") (pinfunction "PA13/SPI1_MISO/I2S1_MCK/USART3_CTS/TIM4_CH3/TIM5_CH4/JTMS-SWDIO_34") (pintype "bidirectional"))
      (node (ref "JP6") (pin "2") (pinfunction "2_2") (pintype "passive"))
    )
    (net (code "94") (name "SW_1") (class "Default")
      (node (ref "IC4") (pin "43") (pinfunction "PB7/I2C1_SDA/USART1_RX/TIM4_CH2_43") (pintype "bidirectional"))
      (node (ref "SW1") (pin "3") (pinfunction "3_3") (pintype "passive"))
      (node (ref "SW1") (pin "4") (pinfunction "4_4") (pintype "passive"))
    )
    (net (code "95") (name "SW_2") (class "Default")
      (node (ref "IC4") (pin "42") (pinfunction "PB6/I2C1_SCL/USART1_TX/TIM4_CH1_42") (pintype "bidirectional"))
      (node (ref "SW2") (pin "3") (pinfunction "3_3") (pintype "passive"))
      (node (ref "SW2") (pin "4") (pinfunction "4_4") (pintype "passive"))
    )
    (net (code "96") (name "TIMBRE_ATT") (class "Default")
      (node (ref "C53") (pin "1") (pinfunction "1_1") (pintype "passive"))
      (node (ref "IC4") (pin "16") (pinfunction "PA6/SPI1_MISO/I2S1_MCK/TIM3_CH1/ADC_IN6/DAC2_OUT1_16") (pintype "bidirectional"))
      (node (ref "R42") (pin "P$2") (pinfunction "S_P$2") (pintype "passive"))
    )
    (net (code "97") (name "TIMBRE_POT") (class "Default")
      (node (ref "C32") (pin "1") (pinfunction "1_1") (pintype "passive"))
      (node (ref "IC4") (pin "13") (pinfunction "PA3/SPI3_MOSI/I2S3_SD/USART2_RX/TIM2_CH4/TIM5_CH4/ADC_IN3_13") (pintype "bidirectional"))
      (node (ref "R7") (pin "P$2") (pinfunction "S_P$2") (pintype "passive"))
    )
    (net (code "98") (name "TX") (class "Default")
      (node (ref "IC4") (pin "45") (pinfunction "PB8/SPI2_SCK/I2S2_CK/I2C1_SCL/USART3_TX/CAN_RX/TIM4_CH3_45") (pintype "bidirectional"))
      (node (ref "R10") (pin "2") (pinfunction "2_2") (pintype "passive"))
    )
    (net (code "99") (name "VCC") (class "Default")
      (node (ref "C37") (pin "1") (pinfunction "1_1") (pintype "passive"))
      (node (ref "C4") (pin "+") (pinfunction "+_+") (pintype "passive"))
      (node (ref "IC8") (pin "8") (pinfunction "V+_8") (pintype "power_in"))
      (node (ref "L2") (pin "1") (pinfunction "1_1") (pintype "passive"))
    )
    (net (code "100") (name "VEE") (class "Default")
      (node (ref "C45") (pin "2") (pinfunction "2_2") (pintype "passive"))
      (node (ref "C5") (pin "-") (pinfunction "-_-") (pintype "passive"))
      (node (ref "IC8") (pin "4") (pinfunction "V-_4") (pintype "power_in"))
      (node (ref "L3") (pin "1") (pinfunction "1_1") (pintype "passive"))
      (node (ref "R37") (pin "1") (pinfunction "1_1") (pintype "passive"))
    )
    (net (code "101") (name "unconnected-(IC2-SOUT-Pad22)") (class "Default")
      (node (ref "IC2") (pin "22") (pinfunction "SOUT_22") (pintype "bidirectional"))
    )
    (net (code "102") (name "unconnected-(IC4-PA15{slash}SPI1_NSS{slash}I2S1_WS{slash}SPI3_NSS{slash}I2S3_WS{slash}I2C1_SCL{slash}TIM2_CH1_ETR{slash}JTDI-Pad38)") (class "Default")
      (node (ref "IC4") (pin "38") (pinfunction "PA15/SPI1_NSS/I2S1_WS/SPI3_NSS/I2S3_WS/I2C1_SCL/TIM2_CH1_ETR/JTDI_38") (pintype "bidirectional"))
    )
    (net (code "103") (name "unconnected-(IC4-PB3{slash}SPI1_SCK{slash}I2S1_CK{slash}SPI3_SCK{slash}I2S3_CK{slash}USART2_TX{slash}TIM2_CH2{slash}JTDO{slash}SPI3_SCK{slash}JTDO-Pad39)") (class "Default")
      (node (ref "IC4") (pin "39") (pinfunction "PB3/SPI1_SCK/I2S1_CK/SPI3_SCK/I2S3_CK/USART2_TX/TIM2_CH2/JTDO/SPI3_SCK/JTDO_39") (pintype "bidirectional"))
    )
    (net (code "104") (name "unconnected-(IC4-PB4{slash}SPI1_MISO{slash}I2S1_MCK{slash}SPI3_MISO{slash}I2S3_MCK{slash}USART2_RX{slash}TIM3_CH1{slash}NJTRST-Pad40)") (class "Default")
      (node (ref "IC4") (pin "40") (pinfunction "PB4/SPI1_MISO/I2S1_MCK/SPI3_MISO/I2S3_MCK/USART2_RX/TIM3_CH1/NJTRST_40") (pintype "bidirectional"))
    )
    (net (code "105") (name "unconnected-(IC4-PB5{slash}SPI1_MOSI{slash}I2S1_SD{slash}SPI3_MOSI{slash}I2S3_SD{slash}I2C1_SMBAI{slash}USART2_CK{slash}TIM3_CH2-Pad41)") (class "Default")
      (node (ref "IC4") (pin "41") (pinfunction "PB5/SPI1_MOSI/I2S1_SD/SPI3_MOSI/I2S3_SD/I2C1_SMBAI/USART2_CK/TIM3_CH2_41") (pintype "bidirectional"))
    )
    (net (code "106") (name "unconnected-(IC4-PC13{slash}TIMESTAMP{slash}RTC_TAMPER1-Pad2)") (class "Default")
      (node (ref "IC4") (pin "2") (pinfunction "PC13/TIMESTAMP/RTC_TAMPER1_2") (pintype "bidirectional"))
    )
    (net (code "107") (name "unconnected-(IC4-PC14{slash}OSC32_IN-Pad3)") (class "Default")
      (node (ref "IC4") (pin "3") (pinfunction "PC14/OSC32_IN_3") (pintype "bidirectional"))
    )
    (net (code "108") (name "unconnected-(IC4-PC15{slash}OSC32_OUT-Pad4)") (class "Default")
      (node (ref "IC4") (pin "4") (pinfunction "PC15/OSC32_OUT_4") (pintype "bidirectional"))
    )
    (net (code "109") (name "unconnected-(J9-2-PadP2)") (class "Default")
      (node (ref "J9") (pin "P2") (pinfunction "2_P2") (pintype "passive"))
    )
    (net (code "110") (name "unconnected-(J10-2-PadP2)") (class "Default")
      (node (ref "J10") (pin "P2") (pinfunction "2_P2") (pintype "passive"))
    )
  )
)
